# Testpoints.net
KiCad netlist of a schematic drawn in Altium Designer
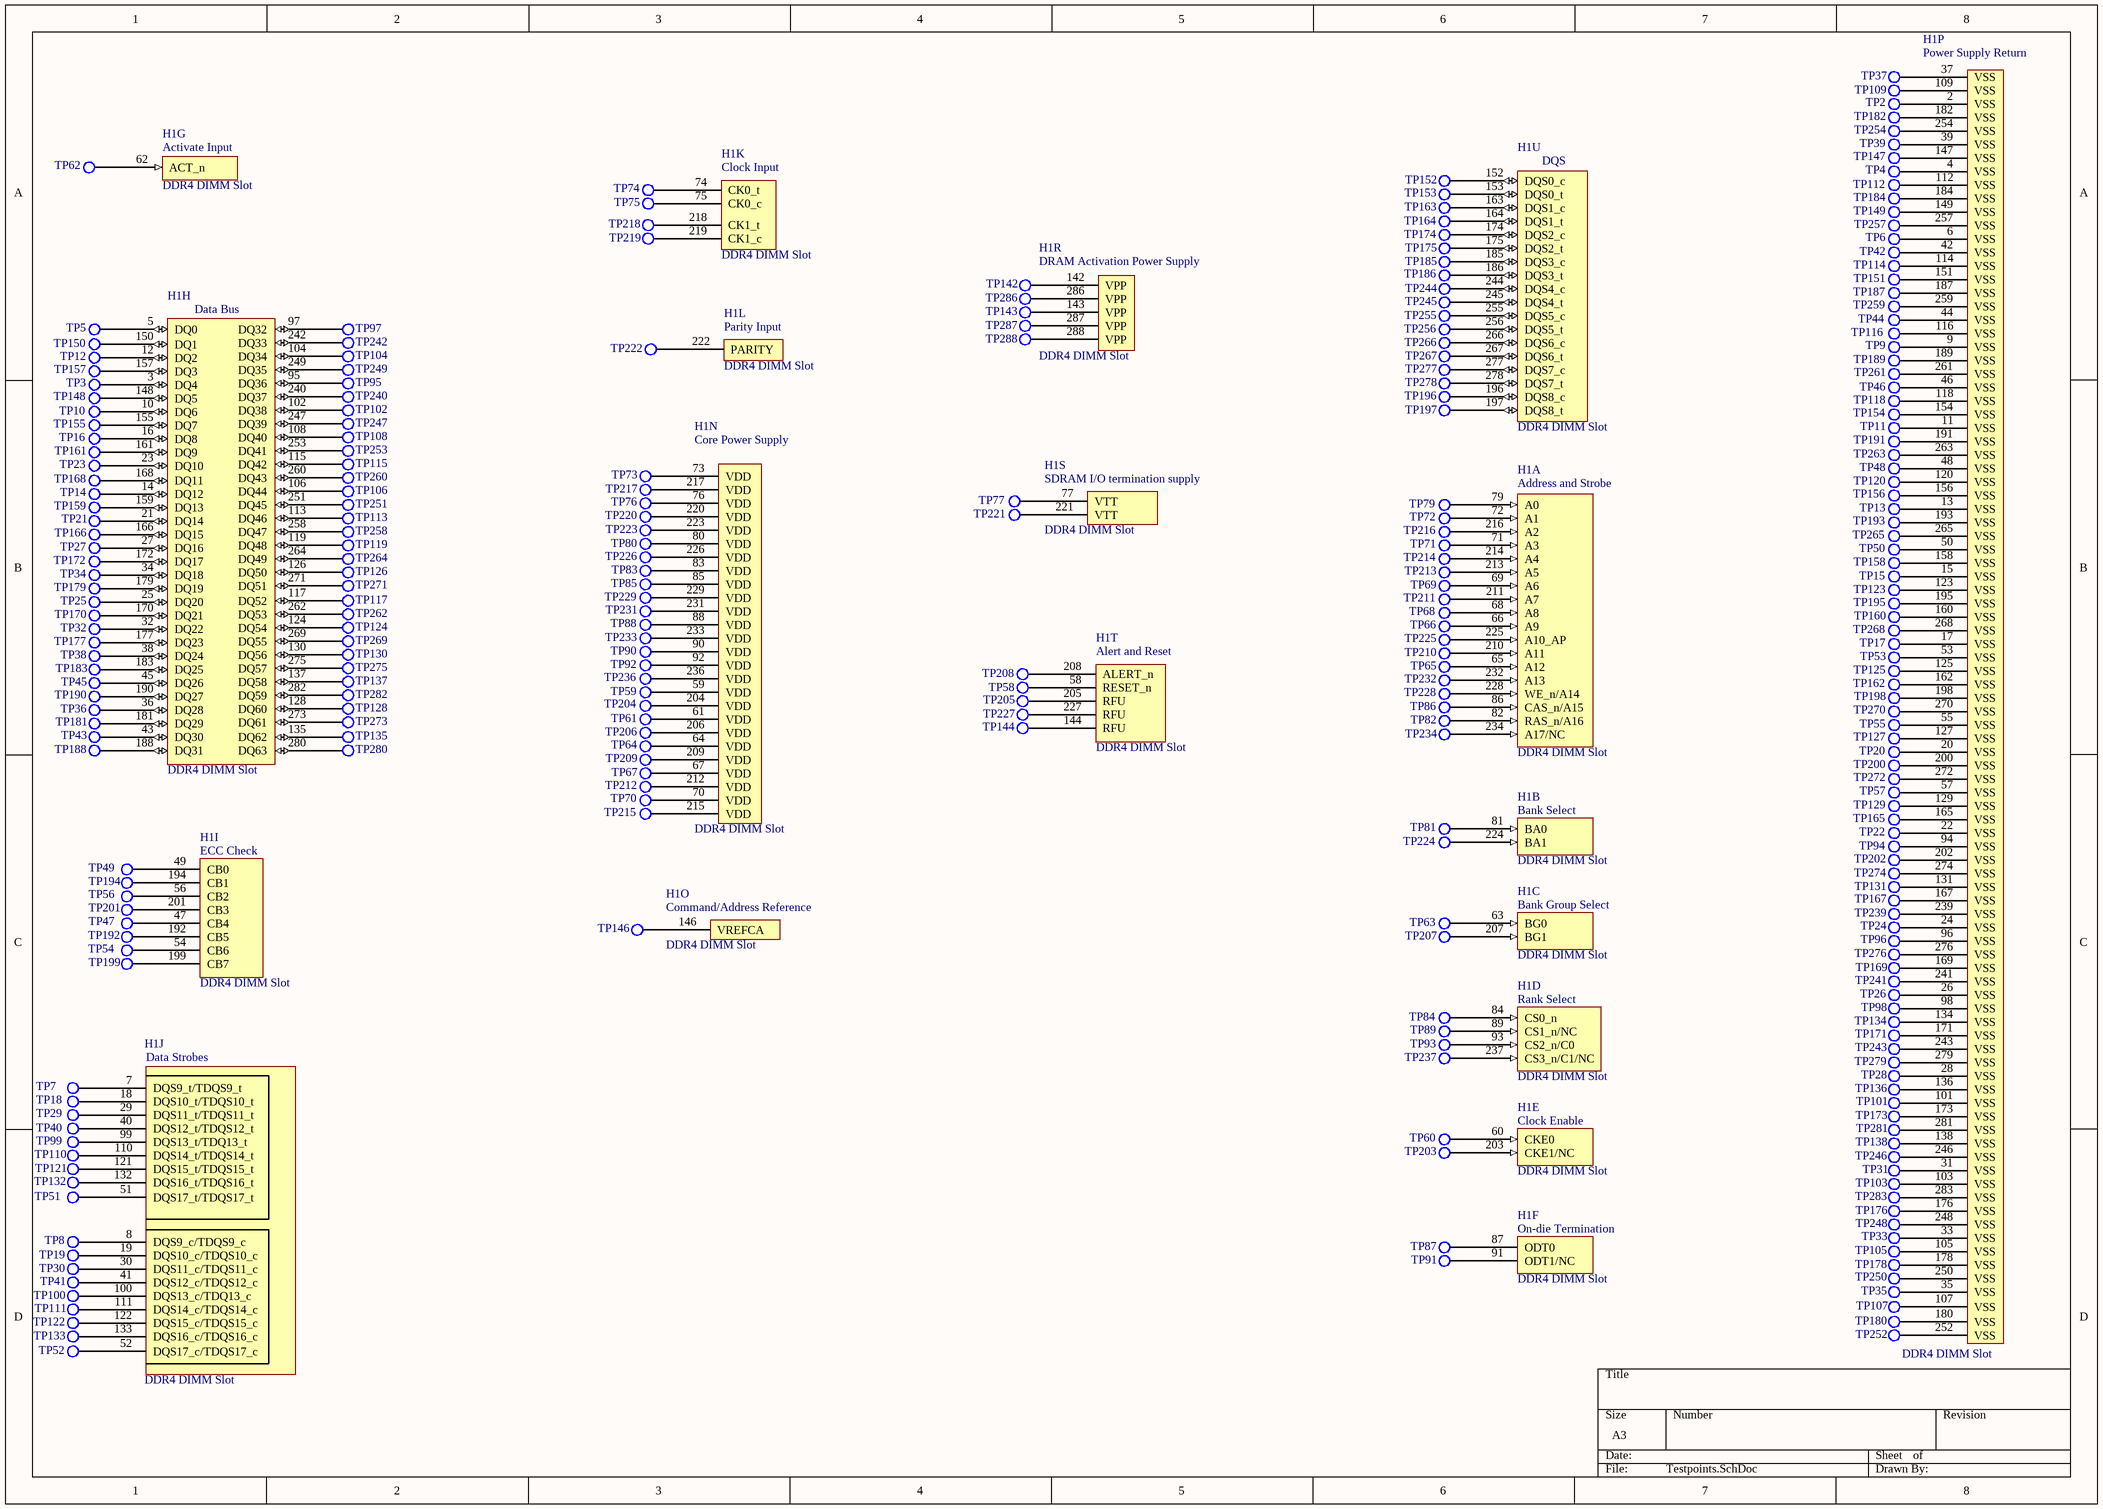
[diagram p0: Testpoints.SchDoc]

(export (version "E")
  (design (tool "Eeschema 10.0.6"))
  (components
    (comp (ref "H1")
      (value "DDR4 DIMM Slot")
      (footprint "DDR4 DIMM Slot")
      (libsource (lib "RouterIntLib") (part "DDR4 DIMM Slot"))
    )
    (comp (ref "TP2")
      (value "Test Point")
      (footprint "Test Point")
      (libsource (lib "RouterIntLib") (part "Test Point"))
    )
    (comp (ref "TP3")
      (value "Test Point")
      (footprint "Test Point")
      (libsource (lib "RouterIntLib") (part "Test Point"))
    )
    (comp (ref "TP4")
      (value "Test Point")
      (footprint "Test Point")
      (libsource (lib "RouterIntLib") (part "Test Point"))
    )
    (comp (ref "TP5")
      (value "Test Point")
      (footprint "Test Point")
      (libsource (lib "RouterIntLib") (part "Test Point"))
    )
    (comp (ref "TP6")
      (value "Test Point")
      (footprint "Test Point")
      (libsource (lib "RouterIntLib") (part "Test Point"))
    )
    (comp (ref "TP7")
      (value "Test Point")
      (footprint "Test Point")
      (libsource (lib "RouterIntLib") (part "Test Point"))
    )
    (comp (ref "TP8")
      (value "Test Point")
      (footprint "Test Point")
      (libsource (lib "RouterIntLib") (part "Test Point"))
    )
    (comp (ref "TP9")
      (value "Test Point")
      (footprint "Test Point")
      (libsource (lib "RouterIntLib") (part "Test Point"))
    )
    (comp (ref "TP10")
      (value "Test Point")
      (footprint "Test Point")
      (libsource (lib "RouterIntLib") (part "Test Point"))
    )
    (comp (ref "TP11")
      (value "Test Point")
      (footprint "Test Point")
      (libsource (lib "RouterIntLib") (part "Test Point"))
    )
    (comp (ref "TP12")
      (value "Test Point")
      (footprint "Test Point")
      (libsource (lib "RouterIntLib") (part "Test Point"))
    )
    (comp (ref "TP13")
      (value "Test Point")
      (footprint "Test Point")
      (libsource (lib "RouterIntLib") (part "Test Point"))
    )
    (comp (ref "TP14")
      (value "Test Point")
      (footprint "Test Point")
      (libsource (lib "RouterIntLib") (part "Test Point"))
    )
    (comp (ref "TP15")
      (value "Test Point")
      (footprint "Test Point")
      (libsource (lib "RouterIntLib") (part "Test Point"))
    )
    (comp (ref "TP16")
      (value "Test Point")
      (footprint "Test Point")
      (libsource (lib "RouterIntLib") (part "Test Point"))
    )
    (comp (ref "TP17")
      (value "Test Point")
      (footprint "Test Point")
      (libsource (lib "RouterIntLib") (part "Test Point"))
    )
    (comp (ref "TP18")
      (value "Test Point")
      (footprint "Test Point")
      (libsource (lib "RouterIntLib") (part "Test Point"))
    )
    (comp (ref "TP19")
      (value "Test Point")
      (footprint "Test Point")
      (libsource (lib "RouterIntLib") (part "Test Point"))
    )
    (comp (ref "TP20")
      (value "Test Point")
      (footprint "Test Point")
      (libsource (lib "RouterIntLib") (part "Test Point"))
    )
    (comp (ref "TP21")
      (value "Test Point")
      (footprint "Test Point")
      (libsource (lib "RouterIntLib") (part "Test Point"))
    )
    (comp (ref "TP22")
      (value "Test Point")
      (footprint "Test Point")
      (libsource (lib "RouterIntLib") (part "Test Point"))
    )
    (comp (ref "TP23")
      (value "Test Point")
      (footprint "Test Point")
      (libsource (lib "RouterIntLib") (part "Test Point"))
    )
    (comp (ref "TP24")
      (value "Test Point")
      (footprint "Test Point")
      (libsource (lib "RouterIntLib") (part "Test Point"))
    )
    (comp (ref "TP25")
      (value "Test Point")
      (footprint "Test Point")
      (libsource (lib "RouterIntLib") (part "Test Point"))
    )
    (comp (ref "TP26")
      (value "Test Point")
      (footprint "Test Point")
      (libsource (lib "RouterIntLib") (part "Test Point"))
    )
    (comp (ref "TP27")
      (value "Test Point")
      (footprint "Test Point")
      (libsource (lib "RouterIntLib") (part "Test Point"))
    )
    (comp (ref "TP28")
      (value "Test Point")
      (footprint "Test Point")
      (libsource (lib "RouterIntLib") (part "Test Point"))
    )
    (comp (ref "TP29")
      (value "Test Point")
      (footprint "Test Point")
      (libsource (lib "RouterIntLib") (part "Test Point"))
    )
    (comp (ref "TP30")
      (value "Test Point")
      (footprint "Test Point")
      (libsource (lib "RouterIntLib") (part "Test Point"))
    )
    (comp (ref "TP31")
      (value "Test Point")
      (footprint "Test Point")
      (libsource (lib "RouterIntLib") (part "Test Point"))
    )
    (comp (ref "TP32")
      (value "Test Point")
      (footprint "Test Point")
      (libsource (lib "RouterIntLib") (part "Test Point"))
    )
    (comp (ref "TP33")
      (value "Test Point")
      (footprint "Test Point")
      (libsource (lib "RouterIntLib") (part "Test Point"))
    )
    (comp (ref "TP34")
      (value "Test Point")
      (footprint "Test Point")
      (libsource (lib "RouterIntLib") (part "Test Point"))
    )
    (comp (ref "TP35")
      (value "Test Point")
      (footprint "Test Point")
      (libsource (lib "RouterIntLib") (part "Test Point"))
    )
    (comp (ref "TP36")
      (value "Test Point")
      (footprint "Test Point")
      (libsource (lib "RouterIntLib") (part "Test Point"))
    )
    (comp (ref "TP37")
      (value "Test Point")
      (footprint "Test Point")
      (libsource (lib "RouterIntLib") (part "Test Point"))
    )
    (comp (ref "TP38")
      (value "Test Point")
      (footprint "Test Point")
      (libsource (lib "RouterIntLib") (part "Test Point"))
    )
    (comp (ref "TP39")
      (value "Test Point")
      (footprint "Test Point")
      (libsource (lib "RouterIntLib") (part "Test Point"))
    )
    (comp (ref "TP40")
      (value "Test Point")
      (footprint "Test Point")
      (libsource (lib "RouterIntLib") (part "Test Point"))
    )
    (comp (ref "TP41")
      (value "Test Point")
      (footprint "Test Point")
      (libsource (lib "RouterIntLib") (part "Test Point"))
    )
    (comp (ref "TP42")
      (value "Test Point")
      (footprint "Test Point")
      (libsource (lib "RouterIntLib") (part "Test Point"))
    )
    (comp (ref "TP43")
      (value "Test Point")
      (footprint "Test Point")
      (libsource (lib "RouterIntLib") (part "Test Point"))
    )
    (comp (ref "TP44")
      (value "Test Point")
      (footprint "Test Point")
      (libsource (lib "RouterIntLib") (part "Test Point"))
    )
    (comp (ref "TP45")
      (value "Test Point")
      (footprint "Test Point")
      (libsource (lib "RouterIntLib") (part "Test Point"))
    )
    (comp (ref "TP46")
      (value "Test Point")
      (footprint "Test Point")
      (libsource (lib "RouterIntLib") (part "Test Point"))
    )
    (comp (ref "TP47")
      (value "Test Point")
      (footprint "Test Point")
      (libsource (lib "RouterIntLib") (part "Test Point"))
    )
    (comp (ref "TP48")
      (value "Test Point")
      (footprint "Test Point")
      (libsource (lib "RouterIntLib") (part "Test Point"))
    )
    (comp (ref "TP49")
      (value "Test Point")
      (footprint "Test Point")
      (libsource (lib "RouterIntLib") (part "Test Point"))
    )
    (comp (ref "TP50")
      (value "Test Point")
      (footprint "Test Point")
      (libsource (lib "RouterIntLib") (part "Test Point"))
    )
    (comp (ref "TP51")
      (value "Test Point")
      (footprint "Test Point")
      (libsource (lib "RouterIntLib") (part "Test Point"))
    )
    (comp (ref "TP52")
      (value "Test Point")
      (footprint "Test Point")
      (libsource (lib "RouterIntLib") (part "Test Point"))
    )
    (comp (ref "TP53")
      (value "Test Point")
      (footprint "Test Point")
      (libsource (lib "RouterIntLib") (part "Test Point"))
    )
    (comp (ref "TP54")
      (value "Test Point")
      (footprint "Test Point")
      (libsource (lib "RouterIntLib") (part "Test Point"))
    )
    (comp (ref "TP55")
      (value "Test Point")
      (footprint "Test Point")
      (libsource (lib "RouterIntLib") (part "Test Point"))
    )
    (comp (ref "TP56")
      (value "Test Point")
      (footprint "Test Point")
      (libsource (lib "RouterIntLib") (part "Test Point"))
    )
    (comp (ref "TP57")
      (value "Test Point")
      (footprint "Test Point")
      (libsource (lib "RouterIntLib") (part "Test Point"))
    )
    (comp (ref "TP58")
      (value "Test Point")
      (footprint "Test Point")
      (libsource (lib "RouterIntLib") (part "Test Point"))
    )
    (comp (ref "TP59")
      (value "Test Point")
      (footprint "Test Point")
      (libsource (lib "RouterIntLib") (part "Test Point"))
    )
    (comp (ref "TP60")
      (value "Test Point")
      (footprint "Test Point")
      (libsource (lib "RouterIntLib") (part "Test Point"))
    )
    (comp (ref "TP61")
      (value "Test Point")
      (footprint "Test Point")
      (libsource (lib "RouterIntLib") (part "Test Point"))
    )
    (comp (ref "TP62")
      (value "Test Point")
      (footprint "Test Point")
      (libsource (lib "RouterIntLib") (part "Test Point"))
    )
    (comp (ref "TP63")
      (value "Test Point")
      (footprint "Test Point")
      (libsource (lib "RouterIntLib") (part "Test Point"))
    )
    (comp (ref "TP64")
      (value "Test Point")
      (footprint "Test Point")
      (libsource (lib "RouterIntLib") (part "Test Point"))
    )
    (comp (ref "TP65")
      (value "Test Point")
      (footprint "Test Point")
      (libsource (lib "RouterIntLib") (part "Test Point"))
    )
    (comp (ref "TP66")
      (value "Test Point")
      (footprint "Test Point")
      (libsource (lib "RouterIntLib") (part "Test Point"))
    )
    (comp (ref "TP67")
      (value "Test Point")
      (footprint "Test Point")
      (libsource (lib "RouterIntLib") (part "Test Point"))
    )
    (comp (ref "TP68")
      (value "Test Point")
      (footprint "Test Point")
      (libsource (lib "RouterIntLib") (part "Test Point"))
    )
    (comp (ref "TP69")
      (value "Test Point")
      (footprint "Test Point")
      (libsource (lib "RouterIntLib") (part "Test Point"))
    )
    (comp (ref "TP70")
      (value "Test Point")
      (footprint "Test Point")
      (libsource (lib "RouterIntLib") (part "Test Point"))
    )
    (comp (ref "TP71")
      (value "Test Point")
      (footprint "Test Point")
      (libsource (lib "RouterIntLib") (part "Test Point"))
    )
    (comp (ref "TP72")
      (value "Test Point")
      (footprint "Test Point")
      (libsource (lib "RouterIntLib") (part "Test Point"))
    )
    (comp (ref "TP73")
      (value "Test Point")
      (footprint "Test Point")
      (libsource (lib "RouterIntLib") (part "Test Point"))
    )
    (comp (ref "TP74")
      (value "Test Point")
      (footprint "Test Point")
      (libsource (lib "RouterIntLib") (part "Test Point"))
    )
    (comp (ref "TP75")
      (value "Test Point")
      (footprint "Test Point")
      (libsource (lib "RouterIntLib") (part "Test Point"))
    )
    (comp (ref "TP76")
      (value "Test Point")
      (footprint "Test Point")
      (libsource (lib "RouterIntLib") (part "Test Point"))
    )
    (comp (ref "TP77")
      (value "Test Point")
      (footprint "Test Point")
      (libsource (lib "RouterIntLib") (part "Test Point"))
    )
    (comp (ref "TP79")
      (value "Test Point")
      (footprint "Test Point")
      (libsource (lib "RouterIntLib") (part "Test Point"))
    )
    (comp (ref "TP80")
      (value "Test Point")
      (footprint "Test Point")
      (libsource (lib "RouterIntLib") (part "Test Point"))
    )
    (comp (ref "TP81")
      (value "Test Point")
      (footprint "Test Point")
      (libsource (lib "RouterIntLib") (part "Test Point"))
    )
    (comp (ref "TP82")
      (value "Test Point")
      (footprint "Test Point")
      (libsource (lib "RouterIntLib") (part "Test Point"))
    )
    (comp (ref "TP83")
      (value "Test Point")
      (footprint "Test Point")
      (libsource (lib "RouterIntLib") (part "Test Point"))
    )
    (comp (ref "TP84")
      (value "Test Point")
      (footprint "Test Point")
      (libsource (lib "RouterIntLib") (part "Test Point"))
    )
    (comp (ref "TP85")
      (value "Test Point")
      (footprint "Test Point")
      (libsource (lib "RouterIntLib") (part "Test Point"))
    )
    (comp (ref "TP86")
      (value "Test Point")
      (footprint "Test Point")
      (libsource (lib "RouterIntLib") (part "Test Point"))
    )
    (comp (ref "TP87")
      (value "Test Point")
      (footprint "Test Point")
      (libsource (lib "RouterIntLib") (part "Test Point"))
    )
    (comp (ref "TP88")
      (value "Test Point")
      (footprint "Test Point")
      (libsource (lib "RouterIntLib") (part "Test Point"))
    )
    (comp (ref "TP89")
      (value "Test Point")
      (footprint "Test Point")
      (libsource (lib "RouterIntLib") (part "Test Point"))
    )
    (comp (ref "TP90")
      (value "Test Point")
      (footprint "Test Point")
      (libsource (lib "RouterIntLib") (part "Test Point"))
    )
    (comp (ref "TP91")
      (value "Test Point")
      (footprint "Test Point")
      (libsource (lib "RouterIntLib") (part "Test Point"))
    )
    (comp (ref "TP92")
      (value "Test Point")
      (footprint "Test Point")
      (libsource (lib "RouterIntLib") (part "Test Point"))
    )
    (comp (ref "TP93")
      (value "Test Point")
      (footprint "Test Point")
      (libsource (lib "RouterIntLib") (part "Test Point"))
    )
    (comp (ref "TP94")
      (value "Test Point")
      (footprint "Test Point")
      (libsource (lib "RouterIntLib") (part "Test Point"))
    )
    (comp (ref "TP95")
      (value "Test Point")
      (footprint "Test Point")
      (libsource (lib "RouterIntLib") (part "Test Point"))
    )
    (comp (ref "TP96")
      (value "Test Point")
      (footprint "Test Point")
      (libsource (lib "RouterIntLib") (part "Test Point"))
    )
    (comp (ref "TP97")
      (value "Test Point")
      (footprint "Test Point")
      (libsource (lib "RouterIntLib") (part "Test Point"))
    )
    (comp (ref "TP98")
      (value "Test Point")
      (footprint "Test Point")
      (libsource (lib "RouterIntLib") (part "Test Point"))
    )
    (comp (ref "TP99")
      (value "Test Point")
      (footprint "Test Point")
      (libsource (lib "RouterIntLib") (part "Test Point"))
    )
    (comp (ref "TP100")
      (value "Test Point")
      (footprint "Test Point")
      (libsource (lib "RouterIntLib") (part "Test Point"))
    )
    (comp (ref "TP101")
      (value "Test Point")
      (footprint "Test Point")
      (libsource (lib "RouterIntLib") (part "Test Point"))
    )
    (comp (ref "TP102")
      (value "Test Point")
      (footprint "Test Point")
      (libsource (lib "RouterIntLib") (part "Test Point"))
    )
    (comp (ref "TP103")
      (value "Test Point")
      (footprint "Test Point")
      (libsource (lib "RouterIntLib") (part "Test Point"))
    )
    (comp (ref "TP104")
      (value "Test Point")
      (footprint "Test Point")
      (libsource (lib "RouterIntLib") (part "Test Point"))
    )
    (comp (ref "TP105")
      (value "Test Point")
      (footprint "Test Point")
      (libsource (lib "RouterIntLib") (part "Test Point"))
    )
    (comp (ref "TP106")
      (value "Test Point")
      (footprint "Test Point")
      (libsource (lib "RouterIntLib") (part "Test Point"))
    )
    (comp (ref "TP107")
      (value "Test Point")
      (footprint "Test Point")
      (libsource (lib "RouterIntLib") (part "Test Point"))
    )
    (comp (ref "TP108")
      (value "Test Point")
      (footprint "Test Point")
      (libsource (lib "RouterIntLib") (part "Test Point"))
    )
    (comp (ref "TP109")
      (value "Test Point")
      (footprint "Test Point")
      (libsource (lib "RouterIntLib") (part "Test Point"))
    )
    (comp (ref "TP110")
      (value "Test Point")
      (footprint "Test Point")
      (libsource (lib "RouterIntLib") (part "Test Point"))
    )
    (comp (ref "TP111")
      (value "Test Point")
      (footprint "Test Point")
      (libsource (lib "RouterIntLib") (part "Test Point"))
    )
    (comp (ref "TP112")
      (value "Test Point")
      (footprint "Test Point")
      (libsource (lib "RouterIntLib") (part "Test Point"))
    )
    (comp (ref "TP113")
      (value "Test Point")
      (footprint "Test Point")
      (libsource (lib "RouterIntLib") (part "Test Point"))
    )
    (comp (ref "TP114")
      (value "Test Point")
      (footprint "Test Point")
      (libsource (lib "RouterIntLib") (part "Test Point"))
    )
    (comp (ref "TP115")
      (value "Test Point")
      (footprint "Test Point")
      (libsource (lib "RouterIntLib") (part "Test Point"))
    )
    (comp (ref "TP116")
      (value "Test Point")
      (footprint "Test Point")
      (libsource (lib "RouterIntLib") (part "Test Point"))
    )
    (comp (ref "TP117")
      (value "Test Point")
      (footprint "Test Point")
      (libsource (lib "RouterIntLib") (part "Test Point"))
    )
    (comp (ref "TP118")
      (value "Test Point")
      (footprint "Test Point")
      (libsource (lib "RouterIntLib") (part "Test Point"))
    )
    (comp (ref "TP119")
      (value "Test Point")
      (footprint "Test Point")
      (libsource (lib "RouterIntLib") (part "Test Point"))
    )
    (comp (ref "TP120")
      (value "Test Point")
      (footprint "Test Point")
      (libsource (lib "RouterIntLib") (part "Test Point"))
    )
    (comp (ref "TP121")
      (value "Test Point")
      (footprint "Test Point")
      (libsource (lib "RouterIntLib") (part "Test Point"))
    )
    (comp (ref "TP122")
      (value "Test Point")
      (footprint "Test Point")
      (libsource (lib "RouterIntLib") (part "Test Point"))
    )
    (comp (ref "TP123")
      (value "Test Point")
      (footprint "Test Point")
      (libsource (lib "RouterIntLib") (part "Test Point"))
    )
    (comp (ref "TP124")
      (value "Test Point")
      (footprint "Test Point")
      (libsource (lib "RouterIntLib") (part "Test Point"))
    )
    (comp (ref "TP125")
      (value "Test Point")
      (footprint "Test Point")
      (libsource (lib "RouterIntLib") (part "Test Point"))
    )
    (comp (ref "TP126")
      (value "Test Point")
      (footprint "Test Point")
      (libsource (lib "RouterIntLib") (part "Test Point"))
    )
    (comp (ref "TP127")
      (value "Test Point")
      (footprint "Test Point")
      (libsource (lib "RouterIntLib") (part "Test Point"))
    )
    (comp (ref "TP128")
      (value "Test Point")
      (footprint "Test Point")
      (libsource (lib "RouterIntLib") (part "Test Point"))
    )
    (comp (ref "TP129")
      (value "Test Point")
      (footprint "Test Point")
      (libsource (lib "RouterIntLib") (part "Test Point"))
    )
    (comp (ref "TP130")
      (value "Test Point")
      (footprint "Test Point")
      (libsource (lib "RouterIntLib") (part "Test Point"))
    )
    (comp (ref "TP131")
      (value "Test Point")
      (footprint "Test Point")
      (libsource (lib "RouterIntLib") (part "Test Point"))
    )
    (comp (ref "TP132")
      (value "Test Point")
      (footprint "Test Point")
      (libsource (lib "RouterIntLib") (part "Test Point"))
    )
    (comp (ref "TP133")
      (value "Test Point")
      (footprint "Test Point")
      (libsource (lib "RouterIntLib") (part "Test Point"))
    )
    (comp (ref "TP134")
      (value "Test Point")
      (footprint "Test Point")
      (libsource (lib "RouterIntLib") (part "Test Point"))
    )
    (comp (ref "TP135")
      (value "Test Point")
      (footprint "Test Point")
      (libsource (lib "RouterIntLib") (part "Test Point"))
    )
    (comp (ref "TP136")
      (value "Test Point")
      (footprint "Test Point")
      (libsource (lib "RouterIntLib") (part "Test Point"))
    )
    (comp (ref "TP137")
      (value "Test Point")
      (footprint "Test Point")
      (libsource (lib "RouterIntLib") (part "Test Point"))
    )
    (comp (ref "TP138")
      (value "Test Point")
      (footprint "Test Point")
      (libsource (lib "RouterIntLib") (part "Test Point"))
    )
    (comp (ref "TP142")
      (value "Test Point")
      (footprint "Test Point")
      (libsource (lib "RouterIntLib") (part "Test Point"))
    )
    (comp (ref "TP143")
      (value "Test Point")
      (footprint "Test Point")
      (libsource (lib "RouterIntLib") (part "Test Point"))
    )
    (comp (ref "TP144")
      (value "Test Point")
      (footprint "Test Point")
      (libsource (lib "RouterIntLib") (part "Test Point"))
    )
    (comp (ref "TP146")
      (value "Test Point")
      (footprint "Test Point")
      (libsource (lib "RouterIntLib") (part "Test Point"))
    )
    (comp (ref "TP147")
      (value "Test Point")
      (footprint "Test Point")
      (libsource (lib "RouterIntLib") (part "Test Point"))
    )
    (comp (ref "TP148")
      (value "Test Point")
      (footprint "Test Point")
      (libsource (lib "RouterIntLib") (part "Test Point"))
    )
    (comp (ref "TP149")
      (value "Test Point")
      (footprint "Test Point")
      (libsource (lib "RouterIntLib") (part "Test Point"))
    )
    (comp (ref "TP150")
      (value "Test Point")
      (footprint "Test Point")
      (libsource (lib "RouterIntLib") (part "Test Point"))
    )
    (comp (ref "TP151")
      (value "Test Point")
      (footprint "Test Point")
      (libsource (lib "RouterIntLib") (part "Test Point"))
    )
    (comp (ref "TP152")
      (value "Test Point")
      (footprint "Test Point")
      (libsource (lib "RouterIntLib") (part "Test Point"))
    )
    (comp (ref "TP153")
      (value "Test Point")
      (footprint "Test Point")
      (libsource (lib "RouterIntLib") (part "Test Point"))
    )
    (comp (ref "TP154")
      (value "Test Point")
      (footprint "Test Point")
      (libsource (lib "RouterIntLib") (part "Test Point"))
    )
    (comp (ref "TP155")
      (value "Test Point")
      (footprint "Test Point")
      (libsource (lib "RouterIntLib") (part "Test Point"))
    )
    (comp (ref "TP156")
      (value "Test Point")
      (footprint "Test Point")
      (libsource (lib "RouterIntLib") (part "Test Point"))
    )
    (comp (ref "TP157")
      (value "Test Point")
      (footprint "Test Point")
      (libsource (lib "RouterIntLib") (part "Test Point"))
    )
    (comp (ref "TP158")
      (value "Test Point")
      (footprint "Test Point")
      (libsource (lib "RouterIntLib") (part "Test Point"))
    )
    (comp (ref "TP159")
      (value "Test Point")
      (footprint "Test Point")
      (libsource (lib "RouterIntLib") (part "Test Point"))
    )
    (comp (ref "TP160")
      (value "Test Point")
      (footprint "Test Point")
      (libsource (lib "RouterIntLib") (part "Test Point"))
    )
    (comp (ref "TP161")
      (value "Test Point")
      (footprint "Test Point")
      (libsource (lib "RouterIntLib") (part "Test Point"))
    )
    (comp (ref "TP162")
      (value "Test Point")
      (footprint "Test Point")
      (libsource (lib "RouterIntLib") (part "Test Point"))
    )
    (comp (ref "TP163")
      (value "Test Point")
      (footprint "Test Point")
      (libsource (lib "RouterIntLib") (part "Test Point"))
    )
    (comp (ref "TP164")
      (value "Test Point")
      (footprint "Test Point")
      (libsource (lib "RouterIntLib") (part "Test Point"))
    )
    (comp (ref "TP165")
      (value "Test Point")
      (footprint "Test Point")
      (libsource (lib "RouterIntLib") (part "Test Point"))
    )
    (comp (ref "TP166")
      (value "Test Point")
      (footprint "Test Point")
      (libsource (lib "RouterIntLib") (part "Test Point"))
    )
    (comp (ref "TP167")
      (value "Test Point")
      (footprint "Test Point")
      (libsource (lib "RouterIntLib") (part "Test Point"))
    )
    (comp (ref "TP168")
      (value "Test Point")
      (footprint "Test Point")
      (libsource (lib "RouterIntLib") (part "Test Point"))
    )
    (comp (ref "TP169")
      (value "Test Point")
      (footprint "Test Point")
      (libsource (lib "RouterIntLib") (part "Test Point"))
    )
    (comp (ref "TP170")
      (value "Test Point")
      (footprint "Test Point")
      (libsource (lib "RouterIntLib") (part "Test Point"))
    )
    (comp (ref "TP171")
      (value "Test Point")
      (footprint "Test Point")
      (libsource (lib "RouterIntLib") (part "Test Point"))
    )
    (comp (ref "TP172")
      (value "Test Point")
      (footprint "Test Point")
      (libsource (lib "RouterIntLib") (part "Test Point"))
    )
    (comp (ref "TP173")
      (value "Test Point")
      (footprint "Test Point")
      (libsource (lib "RouterIntLib") (part "Test Point"))
    )
    (comp (ref "TP174")
      (value "Test Point")
      (footprint "Test Point")
      (libsource (lib "RouterIntLib") (part "Test Point"))
    )
    (comp (ref "TP175")
      (value "Test Point")
      (footprint "Test Point")
      (libsource (lib "RouterIntLib") (part "Test Point"))
    )
    (comp (ref "TP176")
      (value "Test Point")
      (footprint "Test Point")
      (libsource (lib "RouterIntLib") (part "Test Point"))
    )
    (comp (ref "TP177")
      (value "Test Point")
      (footprint "Test Point")
      (libsource (lib "RouterIntLib") (part "Test Point"))
    )
    (comp (ref "TP178")
      (value "Test Point")
      (footprint "Test Point")
      (libsource (lib "RouterIntLib") (part "Test Point"))
    )
    (comp (ref "TP179")
      (value "Test Point")
      (footprint "Test Point")
      (libsource (lib "RouterIntLib") (part "Test Point"))
    )
    (comp (ref "TP180")
      (value "Test Point")
      (footprint "Test Point")
      (libsource (lib "RouterIntLib") (part "Test Point"))
    )
    (comp (ref "TP181")
      (value "Test Point")
      (footprint "Test Point")
      (libsource (lib "RouterIntLib") (part "Test Point"))
    )
    (comp (ref "TP182")
      (value "Test Point")
      (footprint "Test Point")
      (libsource (lib "RouterIntLib") (part "Test Point"))
    )
    (comp (ref "TP183")
      (value "Test Point")
      (footprint "Test Point")
      (libsource (lib "RouterIntLib") (part "Test Point"))
    )
    (comp (ref "TP184")
      (value "Test Point")
      (footprint "Test Point")
      (libsource (lib "RouterIntLib") (part "Test Point"))
    )
    (comp (ref "TP185")
      (value "Test Point")
      (footprint "Test Point")
      (libsource (lib "RouterIntLib") (part "Test Point"))
    )
    (comp (ref "TP186")
      (value "Test Point")
      (footprint "Test Point")
      (libsource (lib "RouterIntLib") (part "Test Point"))
    )
    (comp (ref "TP187")
      (value "Test Point")
      (footprint "Test Point")
      (libsource (lib "RouterIntLib") (part "Test Point"))
    )
    (comp (ref "TP188")
      (value "Test Point")
      (footprint "Test Point")
      (libsource (lib "RouterIntLib") (part "Test Point"))
    )
    (comp (ref "TP189")
      (value "Test Point")
      (footprint "Test Point")
      (libsource (lib "RouterIntLib") (part "Test Point"))
    )
    (comp (ref "TP190")
      (value "Test Point")
      (footprint "Test Point")
      (libsource (lib "RouterIntLib") (part "Test Point"))
    )
    (comp (ref "TP191")
      (value "Test Point")
      (footprint "Test Point")
      (libsource (lib "RouterIntLib") (part "Test Point"))
    )
    (comp (ref "TP192")
      (value "Test Point")
      (footprint "Test Point")
      (libsource (lib "RouterIntLib") (part "Test Point"))
    )
    (comp (ref "TP193")
      (value "Test Point")
      (footprint "Test Point")
      (libsource (lib "RouterIntLib") (part "Test Point"))
    )
    (comp (ref "TP194")
      (value "Test Point")
      (footprint "Test Point")
      (libsource (lib "RouterIntLib") (part "Test Point"))
    )
    (comp (ref "TP195")
      (value "Test Point")
      (footprint "Test Point")
      (libsource (lib "RouterIntLib") (part "Test Point"))
    )
    (comp (ref "TP196")
      (value "Test Point")
      (footprint "Test Point")
      (libsource (lib "RouterIntLib") (part "Test Point"))
    )
    (comp (ref "TP197")
      (value "Test Point")
      (footprint "Test Point")
      (libsource (lib "RouterIntLib") (part "Test Point"))
    )
    (comp (ref "TP198")
      (value "Test Point")
      (footprint "Test Point")
      (libsource (lib "RouterIntLib") (part "Test Point"))
    )
    (comp (ref "TP199")
      (value "Test Point")
      (footprint "Test Point")
      (libsource (lib "RouterIntLib") (part "Test Point"))
    )
    (comp (ref "TP200")
      (value "Test Point")
      (footprint "Test Point")
      (libsource (lib "RouterIntLib") (part "Test Point"))
    )
    (comp (ref "TP201")
      (value "Test Point")
      (footprint "Test Point")
      (libsource (lib "RouterIntLib") (part "Test Point"))
    )
    (comp (ref "TP202")
      (value "Test Point")
      (footprint "Test Point")
      (libsource (lib "RouterIntLib") (part "Test Point"))
    )
    (comp (ref "TP203")
      (value "Test Point")
      (footprint "Test Point")
      (libsource (lib "RouterIntLib") (part "Test Point"))
    )
    (comp (ref "TP204")
      (value "Test Point")
      (footprint "Test Point")
      (libsource (lib "RouterIntLib") (part "Test Point"))
    )
    (comp (ref "TP205")
      (value "Test Point")
      (footprint "Test Point")
      (libsource (lib "RouterIntLib") (part "Test Point"))
    )
    (comp (ref "TP206")
      (value "Test Point")
      (footprint "Test Point")
      (libsource (lib "RouterIntLib") (part "Test Point"))
    )
    (comp (ref "TP207")
      (value "Test Point")
      (footprint "Test Point")
      (libsource (lib "RouterIntLib") (part "Test Point"))
    )
    (comp (ref "TP208")
      (value "Test Point")
      (footprint "Test Point")
      (libsource (lib "RouterIntLib") (part "Test Point"))
    )
    (comp (ref "TP209")
      (value "Test Point")
      (footprint "Test Point")
      (libsource (lib "RouterIntLib") (part "Test Point"))
    )
    (comp (ref "TP210")
      (value "Test Point")
      (footprint "Test Point")
      (libsource (lib "RouterIntLib") (part "Test Point"))
    )
    (comp (ref "TP211")
      (value "Test Point")
      (footprint "Test Point")
      (libsource (lib "RouterIntLib") (part "Test Point"))
    )
    (comp (ref "TP212")
      (value "Test Point")
      (footprint "Test Point")
      (libsource (lib "RouterIntLib") (part "Test Point"))
    )
    (comp (ref "TP213")
      (value "Test Point")
      (footprint "Test Point")
      (libsource (lib "RouterIntLib") (part "Test Point"))
    )
    (comp (ref "TP214")
      (value "Test Point")
      (footprint "Test Point")
      (libsource (lib "RouterIntLib") (part "Test Point"))
    )
    (comp (ref "TP215")
      (value "Test Point")
      (footprint "Test Point")
      (libsource (lib "RouterIntLib") (part "Test Point"))
    )
    (comp (ref "TP216")
      (value "Test Point")
      (footprint "Test Point")
      (libsource (lib "RouterIntLib") (part "Test Point"))
    )
    (comp (ref "TP217")
      (value "Test Point")
      (footprint "Test Point")
      (libsource (lib "RouterIntLib") (part "Test Point"))
    )
    (comp (ref "TP218")
      (value "Test Point")
      (footprint "Test Point")
      (libsource (lib "RouterIntLib") (part "Test Point"))
    )
    (comp (ref "TP219")
      (value "Test Point")
      (footprint "Test Point")
      (libsource (lib "RouterIntLib") (part "Test Point"))
    )
    (comp (ref "TP220")
      (value "Test Point")
      (footprint "Test Point")
      (libsource (lib "RouterIntLib") (part "Test Point"))
    )
    (comp (ref "TP221")
      (value "Test Point")
      (footprint "Test Point")
      (libsource (lib "RouterIntLib") (part "Test Point"))
    )
    (comp (ref "TP222")
      (value "Test Point")
      (footprint "Test Point")
      (libsource (lib "RouterIntLib") (part "Test Point"))
    )
    (comp (ref "TP223")
      (value "Test Point")
      (footprint "Test Point")
      (libsource (lib "RouterIntLib") (part "Test Point"))
    )
    (comp (ref "TP224")
      (value "Test Point")
      (footprint "Test Point")
      (libsource (lib "RouterIntLib") (part "Test Point"))
    )
    (comp (ref "TP225")
      (value "Test Point")
      (footprint "Test Point")
      (libsource (lib "RouterIntLib") (part "Test Point"))
    )
    (comp (ref "TP226")
      (value "Test Point")
      (footprint "Test Point")
      (libsource (lib "RouterIntLib") (part "Test Point"))
    )
    (comp (ref "TP227")
      (value "Test Point")
      (footprint "Test Point")
      (libsource (lib "RouterIntLib") (part "Test Point"))
    )
    (comp (ref "TP228")
      (value "Test Point")
      (footprint "Test Point")
      (libsource (lib "RouterIntLib") (part "Test Point"))
    )
    (comp (ref "TP229")
      (value "Test Point")
      (footprint "Test Point")
      (libsource (lib "RouterIntLib") (part "Test Point"))
    )
    (comp (ref "TP231")
      (value "Test Point")
      (footprint "Test Point")
      (libsource (lib "RouterIntLib") (part "Test Point"))
    )
    (comp (ref "TP232")
      (value "Test Point")
      (footprint "Test Point")
      (libsource (lib "RouterIntLib") (part "Test Point"))
    )
    (comp (ref "TP233")
      (value "Test Point")
      (footprint "Test Point")
      (libsource (lib "RouterIntLib") (part "Test Point"))
    )
    (comp (ref "TP234")
      (value "Test Point")
      (footprint "Test Point")
      (libsource (lib "RouterIntLib") (part "Test Point"))
    )
    (comp (ref "TP236")
      (value "Test Point")
      (footprint "Test Point")
      (libsource (lib "RouterIntLib") (part "Test Point"))
    )
    (comp (ref "TP237")
      (value "Test Point")
      (footprint "Test Point")
      (libsource (lib "RouterIntLib") (part "Test Point"))
    )
    (comp (ref "TP239")
      (value "Test Point")
      (footprint "Test Point")
      (libsource (lib "RouterIntLib") (part "Test Point"))
    )
    (comp (ref "TP240")
      (value "Test Point")
      (footprint "Test Point")
      (libsource (lib "RouterIntLib") (part "Test Point"))
    )
    (comp (ref "TP241")
      (value "Test Point")
      (footprint "Test Point")
      (libsource (lib "RouterIntLib") (part "Test Point"))
    )
    (comp (ref "TP242")
      (value "Test Point")
      (footprint "Test Point")
      (libsource (lib "RouterIntLib") (part "Test Point"))
    )
    (comp (ref "TP243")
      (value "Test Point")
      (footprint "Test Point")
      (libsource (lib "RouterIntLib") (part "Test Point"))
    )
    (comp (ref "TP244")
      (value "Test Point")
      (footprint "Test Point")
      (libsource (lib "RouterIntLib") (part "Test Point"))
    )
    (comp (ref "TP245")
      (value "Test Point")
      (footprint "Test Point")
      (libsource (lib "RouterIntLib") (part "Test Point"))
    )
    (comp (ref "TP246")
      (value "Test Point")
      (footprint "Test Point")
      (libsource (lib "RouterIntLib") (part "Test Point"))
    )
    (comp (ref "TP247")
      (value "Test Point")
      (footprint "Test Point")
      (libsource (lib "RouterIntLib") (part "Test Point"))
    )
    (comp (ref "TP248")
      (value "Test Point")
      (footprint "Test Point")
      (libsource (lib "RouterIntLib") (part "Test Point"))
    )
    (comp (ref "TP249")
      (value "Test Point")
      (footprint "Test Point")
      (libsource (lib "RouterIntLib") (part "Test Point"))
    )
    (comp (ref "TP250")
      (value "Test Point")
      (footprint "Test Point")
      (libsource (lib "RouterIntLib") (part "Test Point"))
    )
    (comp (ref "TP251")
      (value "Test Point")
      (footprint "Test Point")
      (libsource (lib "RouterIntLib") (part "Test Point"))
    )
    (comp (ref "TP252")
      (value "Test Point")
      (footprint "Test Point")
      (libsource (lib "RouterIntLib") (part "Test Point"))
    )
    (comp (ref "TP253")
      (value "Test Point")
      (footprint "Test Point")
      (libsource (lib "RouterIntLib") (part "Test Point"))
    )
    (comp (ref "TP254")
      (value "Test Point")
      (footprint "Test Point")
      (libsource (lib "RouterIntLib") (part "Test Point"))
    )
    (comp (ref "TP255")
      (value "Test Point")
      (footprint "Test Point")
      (libsource (lib "RouterIntLib") (part "Test Point"))
    )
    (comp (ref "TP256")
      (value "Test Point")
      (footprint "Test Point")
      (libsource (lib "RouterIntLib") (part "Test Point"))
    )
    (comp (ref "TP257")
      (value "Test Point")
      (footprint "Test Point")
      (libsource (lib "RouterIntLib") (part "Test Point"))
    )
    (comp (ref "TP258")
      (value "Test Point")
      (footprint "Test Point")
      (libsource (lib "RouterIntLib") (part "Test Point"))
    )
    (comp (ref "TP259")
      (value "Test Point")
      (footprint "Test Point")
      (libsource (lib "RouterIntLib") (part "Test Point"))
    )
    (comp (ref "TP260")
      (value "Test Point")
      (footprint "Test Point")
      (libsource (lib "RouterIntLib") (part "Test Point"))
    )
    (comp (ref "TP261")
      (value "Test Point")
      (footprint "Test Point")
      (libsource (lib "RouterIntLib") (part "Test Point"))
    )
    (comp (ref "TP262")
      (value "Test Point")
      (footprint "Test Point")
      (libsource (lib "RouterIntLib") (part "Test Point"))
    )
    (comp (ref "TP263")
      (value "Test Point")
      (footprint "Test Point")
      (libsource (lib "RouterIntLib") (part "Test Point"))
    )
    (comp (ref "TP264")
      (value "Test Point")
      (footprint "Test Point")
      (libsource (lib "RouterIntLib") (part "Test Point"))
    )
    (comp (ref "TP265")
      (value "Test Point")
      (footprint "Test Point")
      (libsource (lib "RouterIntLib") (part "Test Point"))
    )
    (comp (ref "TP266")
      (value "Test Point")
      (footprint "Test Point")
      (libsource (lib "RouterIntLib") (part "Test Point"))
    )
    (comp (ref "TP267")
      (value "Test Point")
      (footprint "Test Point")
      (libsource (lib "RouterIntLib") (part "Test Point"))
    )
    (comp (ref "TP268")
      (value "Test Point")
      (footprint "Test Point")
      (libsource (lib "RouterIntLib") (part "Test Point"))
    )
    (comp (ref "TP269")
      (value "Test Point")
      (footprint "Test Point")
      (libsource (lib "RouterIntLib") (part "Test Point"))
    )
    (comp (ref "TP270")
      (value "Test Point")
      (footprint "Test Point")
      (libsource (lib "RouterIntLib") (part "Test Point"))
    )
    (comp (ref "TP271")
      (value "Test Point")
      (footprint "Test Point")
      (libsource (lib "RouterIntLib") (part "Test Point"))
    )
    (comp (ref "TP272")
      (value "Test Point")
      (footprint "Test Point")
      (libsource (lib "RouterIntLib") (part "Test Point"))
    )
    (comp (ref "TP273")
      (value "Test Point")
      (footprint "Test Point")
      (libsource (lib "RouterIntLib") (part "Test Point"))
    )
    (comp (ref "TP274")
      (value "Test Point")
      (footprint "Test Point")
      (libsource (lib "RouterIntLib") (part "Test Point"))
    )
    (comp (ref "TP275")
      (value "Test Point")
      (footprint "Test Point")
      (libsource (lib "RouterIntLib") (part "Test Point"))
    )
    (comp (ref "TP276")
      (value "Test Point")
      (footprint "Test Point")
      (libsource (lib "RouterIntLib") (part "Test Point"))
    )
    (comp (ref "TP277")
      (value "Test Point")
      (footprint "Test Point")
      (libsource (lib "RouterIntLib") (part "Test Point"))
    )
    (comp (ref "TP278")
      (value "Test Point")
      (footprint "Test Point")
      (libsource (lib "RouterIntLib") (part "Test Point"))
    )
    (comp (ref "TP279")
      (value "Test Point")
      (footprint "Test Point")
      (libsource (lib "RouterIntLib") (part "Test Point"))
    )
    (comp (ref "TP280")
      (value "Test Point")
      (footprint "Test Point")
      (libsource (lib "RouterIntLib") (part "Test Point"))
    )
    (comp (ref "TP281")
      (value "Test Point")
      (footprint "Test Point")
      (libsource (lib "RouterIntLib") (part "Test Point"))
    )
    (comp (ref "TP282")
      (value "Test Point")
      (footprint "Test Point")
      (libsource (lib "RouterIntLib") (part "Test Point"))
    )
    (comp (ref "TP283")
      (value "Test Point")
      (footprint "Test Point")
      (libsource (lib "RouterIntLib") (part "Test Point"))
    )
    (comp (ref "TP286")
      (value "Test Point")
      (footprint "Test Point")
      (libsource (lib "RouterIntLib") (part "Test Point"))
    )
    (comp (ref "TP287")
      (value "Test Point")
      (footprint "Test Point")
      (libsource (lib "RouterIntLib") (part "Test Point"))
    )
    (comp (ref "TP288")
      (value "Test Point")
      (footprint "Test Point")
      (libsource (lib "RouterIntLib") (part "Test Point"))
    )
  )
  (nets
    (net (code "1") (name "Net-(H1A-A0)") (class "Default")
      (node (ref "H1") (pin "79") (pinfunction "A0_79") (pintype "input"))
      (node (ref "TP79") (pin "1") (pinfunction "1_1") (pintype "passive"))
    )
    (net (code "2") (name "Net-(H1A-A1)") (class "Default")
      (node (ref "H1") (pin "72") (pinfunction "A1_72") (pintype "input"))
      (node (ref "TP72") (pin "1") (pinfunction "1_1") (pintype "passive"))
    )
    (net (code "3") (name "Net-(H1A-A2)") (class "Default")
      (node (ref "H1") (pin "216") (pinfunction "A2_216") (pintype "input"))
      (node (ref "TP216") (pin "1") (pinfunction "1_1") (pintype "passive"))
    )
    (net (code "4") (name "Net-(H1A-A3)") (class "Default")
      (node (ref "H1") (pin "71") (pinfunction "A3_71") (pintype "input"))
      (node (ref "TP71") (pin "1") (pinfunction "1_1") (pintype "passive"))
    )
    (net (code "5") (name "Net-(H1A-A4)") (class "Default")
      (node (ref "H1") (pin "214") (pinfunction "A4_214") (pintype "input"))
      (node (ref "TP214") (pin "1") (pinfunction "1_1") (pintype "passive"))
    )
    (net (code "6") (name "Net-(H1A-A5)") (class "Default")
      (node (ref "H1") (pin "213") (pinfunction "A5_213") (pintype "input"))
      (node (ref "TP213") (pin "1") (pinfunction "1_1") (pintype "passive"))
    )
    (net (code "7") (name "Net-(H1A-A6)") (class "Default")
      (node (ref "H1") (pin "69") (pinfunction "A6_69") (pintype "input"))
      (node (ref "TP69") (pin "1") (pinfunction "1_1") (pintype "passive"))
    )
    (net (code "8") (name "Net-(H1A-A7)") (class "Default")
      (node (ref "H1") (pin "211") (pinfunction "A7_211") (pintype "input"))
      (node (ref "TP211") (pin "1") (pinfunction "1_1") (pintype "passive"))
    )
    (net (code "9") (name "Net-(H1A-A8)") (class "Default")
      (node (ref "H1") (pin "68") (pinfunction "A8_68") (pintype "input"))
      (node (ref "TP68") (pin "1") (pinfunction "1_1") (pintype "passive"))
    )
    (net (code "10") (name "Net-(H1A-A9)") (class "Default")
      (node (ref "H1") (pin "66") (pinfunction "A9_66") (pintype "input"))
      (node (ref "TP66") (pin "1") (pinfunction "1_1") (pintype "passive"))
    )
    (net (code "11") (name "Net-(H1A-A10_AP)") (class "Default")
      (node (ref "H1") (pin "225") (pinfunction "A10_AP_225") (pintype "input"))
      (node (ref "TP225") (pin "1") (pinfunction "1_1") (pintype "passive"))
    )
    (net (code "12") (name "Net-(H1A-A11)") (class "Default")
      (node (ref "H1") (pin "210") (pinfunction "A11_210") (pintype "input"))
      (node (ref "TP210") (pin "1") (pinfunction "1_1") (pintype "passive"))
    )
    (net (code "13") (name "Net-(H1A-A12)") (class "Default")
      (node (ref "H1") (pin "65") (pinfunction "A12_65") (pintype "input"))
      (node (ref "TP65") (pin "1") (pinfunction "1_1") (pintype "passive"))
    )
    (net (code "14") (name "Net-(H1A-A13)") (class "Default")
      (node (ref "H1") (pin "232") (pinfunction "A13_232") (pintype "input"))
      (node (ref "TP232") (pin "1") (pinfunction "1_1") (pintype "passive"))
    )
    (net (code "15") (name "Net-(H1A-A17{slash}NC)") (class "Default")
      (node (ref "H1") (pin "234") (pinfunction "A17/NC_234") (pintype "input"))
      (node (ref "TP234") (pin "1") (pinfunction "1_1") (pintype "passive"))
    )
    (net (code "16") (name "Net-(H1A-CAS_n{slash}A15)") (class "Default")
      (node (ref "H1") (pin "86") (pinfunction "CAS_n/A15_86") (pintype "input"))
      (node (ref "TP86") (pin "1") (pinfunction "1_1") (pintype "passive"))
    )
    (net (code "17") (name "Net-(H1A-RAS_n{slash}A16)") (class "Default")
      (node (ref "H1") (pin "82") (pinfunction "RAS_n/A16_82") (pintype "input"))
      (node (ref "TP82") (pin "1") (pinfunction "1_1") (pintype "passive"))
    )
    (net (code "18") (name "Net-(H1A-WE_n{slash}A14)") (class "Default")
      (node (ref "H1") (pin "228") (pinfunction "WE_n/A14_228") (pintype "input"))
      (node (ref "TP228") (pin "1") (pinfunction "1_1") (pintype "passive"))
    )
    (net (code "19") (name "Net-(H1B-BA0)") (class "Default")
      (node (ref "H1") (pin "81") (pinfunction "BA0_81") (pintype "input"))
      (node (ref "TP81") (pin "1") (pinfunction "1_1") (pintype "passive"))
    )
    (net (code "20") (name "Net-(H1B-BA1)") (class "Default")
      (node (ref "H1") (pin "224") (pinfunction "BA1_224") (pintype "input"))
      (node (ref "TP224") (pin "1") (pinfunction "1_1") (pintype "passive"))
    )
    (net (code "21") (name "Net-(H1C-BG0)") (class "Default")
      (node (ref "H1") (pin "63") (pinfunction "BG0_63") (pintype "input"))
      (node (ref "TP63") (pin "1") (pinfunction "1_1") (pintype "passive"))
    )
    (net (code "22") (name "Net-(H1C-BG1)") (class "Default")
      (node (ref "H1") (pin "207") (pinfunction "BG1_207") (pintype "input"))
      (node (ref "TP207") (pin "1") (pinfunction "1_1") (pintype "passive"))
    )
    (net (code "23") (name "Net-(H1D-CS0_n)") (class "Default")
      (node (ref "H1") (pin "84") (pinfunction "CS0_n_84") (pintype "input"))
      (node (ref "TP84") (pin "1") (pinfunction "1_1") (pintype "passive"))
    )
    (net (code "24") (name "Net-(H1D-CS1_n{slash}NC)") (class "Default")
      (node (ref "H1") (pin "89") (pinfunction "CS1_n/NC_89") (pintype "input"))
      (node (ref "TP89") (pin "1") (pinfunction "1_1") (pintype "passive"))
    )
    (net (code "25") (name "Net-(H1D-CS2_n{slash}C0)") (class "Default")
      (node (ref "H1") (pin "93") (pinfunction "CS2_n/C0_93") (pintype "input"))
      (node (ref "TP93") (pin "1") (pinfunction "1_1") (pintype "passive"))
    )
    (net (code "26") (name "Net-(H1D-CS3_n{slash}C1{slash}NC)") (class "Default")
      (node (ref "H1") (pin "237") (pinfunction "CS3_n/C1/NC_237") (pintype "input"))
      (node (ref "TP237") (pin "1") (pinfunction "1_1") (pintype "passive"))
    )
    (net (code "27") (name "Net-(H1E-CKE0)") (class "Default")
      (node (ref "H1") (pin "60") (pinfunction "CKE0_60") (pintype "input"))
      (node (ref "TP60") (pin "1") (pinfunction "1_1") (pintype "passive"))
    )
    (net (code "28") (name "Net-(H1E-CKE1{slash}NC)") (class "Default")
      (node (ref "H1") (pin "203") (pinfunction "CKE1/NC_203") (pintype "input"))
      (node (ref "TP203") (pin "1") (pinfunction "1_1") (pintype "passive"))
    )
    (net (code "29") (name "Net-(H1F-ODT0)") (class "Default")
      (node (ref "H1") (pin "87") (pinfunction "ODT0_87") (pintype "passive"))
      (node (ref "TP87") (pin "1") (pinfunction "1_1") (pintype "passive"))
    )
    (net (code "30") (name "Net-(H1F-ODT1{slash}NC)") (class "Default")
      (node (ref "H1") (pin "91") (pinfunction "ODT1/NC_91") (pintype "passive"))
      (node (ref "TP91") (pin "1") (pinfunction "1_1") (pintype "passive"))
    )
    (net (code "31") (name "Net-(H1G-ACT_n)") (class "Default")
      (node (ref "H1") (pin "62") (pinfunction "ACT_n_62") (pintype "input"))
      (node (ref "TP62") (pin "1") (pinfunction "1_1") (pintype "passive"))
    )
    (net (code "32") (name "Net-(H1H-DQ0)") (class "Default")
      (node (ref "H1") (pin "5") (pinfunction "DQ0_5") (pintype "bidirectional"))
      (node (ref "TP5") (pin "1") (pinfunction "1_1") (pintype "passive"))
    )
    (net (code "33") (name "Net-(H1H-DQ1)") (class "Default")
      (node (ref "H1") (pin "150") (pinfunction "DQ1_150") (pintype "bidirectional"))
      (node (ref "TP150") (pin "1") (pinfunction "1_1") (pintype "passive"))
    )
    (net (code "34") (name "Net-(H1H-DQ2)") (class "Default")
      (node (ref "H1") (pin "12") (pinfunction "DQ2_12") (pintype "bidirectional"))
      (node (ref "TP12") (pin "1") (pinfunction "1_1") (pintype "passive"))
    )
    (net (code "35") (name "Net-(H1H-DQ3)") (class "Default")
      (node (ref "H1") (pin "157") (pinfunction "DQ3_157") (pintype "bidirectional"))
      (node (ref "TP157") (pin "1") (pinfunction "1_1") (pintype "passive"))
    )
    (net (code "36") (name "Net-(H1H-DQ4)") (class "Default")
      (node (ref "H1") (pin "3") (pinfunction "DQ4_3") (pintype "bidirectional"))
      (node (ref "TP3") (pin "1") (pinfunction "1_1") (pintype "passive"))
    )
    (net (code "37") (name "Net-(H1H-DQ5)") (class "Default")
      (node (ref "H1") (pin "148") (pinfunction "DQ5_148") (pintype "bidirectional"))
      (node (ref "TP148") (pin "1") (pinfunction "1_1") (pintype "passive"))
    )
    (net (code "38") (name "Net-(H1H-DQ6)") (class "Default")
      (node (ref "H1") (pin "10") (pinfunction "DQ6_10") (pintype "bidirectional"))
      (node (ref "TP10") (pin "1") (pinfunction "1_1") (pintype "passive"))
    )
    (net (code "39") (name "Net-(H1H-DQ7)") (class "Default")
      (node (ref "H1") (pin "155") (pinfunction "DQ7_155") (pintype "bidirectional"))
      (node (ref "TP155") (pin "1") (pinfunction "1_1") (pintype "passive"))
    )
    (net (code "40") (name "Net-(H1H-DQ8)") (class "Default")
      (node (ref "H1") (pin "16") (pinfunction "DQ8_16") (pintype "bidirectional"))
      (node (ref "TP16") (pin "1") (pinfunction "1_1") (pintype "passive"))
    )
    (net (code "41") (name "Net-(H1H-DQ9)") (class "Default")
      (node (ref "H1") (pin "161") (pinfunction "DQ9_161") (pintype "bidirectional"))
      (node (ref "TP161") (pin "1") (pinfunction "1_1") (pintype "passive"))
    )
    (net (code "42") (name "Net-(H1H-DQ10)") (class "Default")
      (node (ref "H1") (pin "23") (pinfunction "DQ10_23") (pintype "bidirectional"))
      (node (ref "TP23") (pin "1") (pinfunction "1_1") (pintype "passive"))
    )
    (net (code "43") (name "Net-(H1H-DQ11)") (class "Default")
      (node (ref "H1") (pin "168") (pinfunction "DQ11_168") (pintype "bidirectional"))
      (node (ref "TP168") (pin "1") (pinfunction "1_1") (pintype "passive"))
    )
    (net (code "44") (name "Net-(H1H-DQ12)") (class "Default")
      (node (ref "H1") (pin "14") (pinfunction "DQ12_14") (pintype "bidirectional"))
      (node (ref "TP14") (pin "1") (pinfunction "1_1") (pintype "passive"))
    )
    (net (code "45") (name "Net-(H1H-DQ13)") (class "Default")
      (node (ref "H1") (pin "159") (pinfunction "DQ13_159") (pintype "bidirectional"))
      (node (ref "TP159") (pin "1") (pinfunction "1_1") (pintype "passive"))
    )
    (net (code "46") (name "Net-(H1H-DQ14)") (class "Default")
      (node (ref "H1") (pin "21") (pinfunction "DQ14_21") (pintype "bidirectional"))
      (node (ref "TP21") (pin "1") (pinfunction "1_1") (pintype "passive"))
    )
    (net (code "47") (name "Net-(H1H-DQ15)") (class "Default")
      (node (ref "H1") (pin "166") (pinfunction "DQ15_166") (pintype "bidirectional"))
      (node (ref "TP166") (pin "1") (pinfunction "1_1") (pintype "passive"))
    )
    (net (code "48") (name "Net-(H1H-DQ16)") (class "Default")
      (node (ref "H1") (pin "27") (pinfunction "DQ16_27") (pintype "bidirectional"))
      (node (ref "TP27") (pin "1") (pinfunction "1_1") (pintype "passive"))
    )
    (net (code "49") (name "Net-(H1H-DQ17)") (class "Default")
      (node (ref "H1") (pin "172") (pinfunction "DQ17_172") (pintype "bidirectional"))
      (node (ref "TP172") (pin "1") (pinfunction "1_1") (pintype "passive"))
    )
    (net (code "50") (name "Net-(H1H-DQ18)") (class "Default")
      (node (ref "H1") (pin "34") (pinfunction "DQ18_34") (pintype "bidirectional"))
      (node (ref "TP34") (pin "1") (pinfunction "1_1") (pintype "passive"))
    )
    (net (code "51") (name "Net-(H1H-DQ19)") (class "Default")
      (node (ref "H1") (pin "179") (pinfunction "DQ19_179") (pintype "bidirectional"))
      (node (ref "TP179") (pin "1") (pinfunction "1_1") (pintype "passive"))
    )
    (net (code "52") (name "Net-(H1H-DQ20)") (class "Default")
      (node (ref "H1") (pin "25") (pinfunction "DQ20_25") (pintype "bidirectional"))
      (node (ref "TP25") (pin "1") (pinfunction "1_1") (pintype "passive"))
    )
    (net (code "53") (name "Net-(H1H-DQ21)") (class "Default")
      (node (ref "H1") (pin "170") (pinfunction "DQ21_170") (pintype "bidirectional"))
      (node (ref "TP170") (pin "1") (pinfunction "1_1") (pintype "passive"))
    )
    (net (code "54") (name "Net-(H1H-DQ22)") (class "Default")
      (node (ref "H1") (pin "32") (pinfunction "DQ22_32") (pintype "bidirectional"))
      (node (ref "TP32") (pin "1") (pinfunction "1_1") (pintype "passive"))
    )
    (net (code "55") (name "Net-(H1H-DQ23)") (class "Default")
      (node (ref "H1") (pin "177") (pinfunction "DQ23_177") (pintype "bidirectional"))
      (node (ref "TP177") (pin "1") (pinfunction "1_1") (pintype "passive"))
    )
    (net (code "56") (name "Net-(H1H-DQ24)") (class "Default")
      (node (ref "H1") (pin "38") (pinfunction "DQ24_38") (pintype "bidirectional"))
      (node (ref "TP38") (pin "1") (pinfunction "1_1") (pintype "passive"))
    )
    (net (code "57") (name "Net-(H1H-DQ25)") (class "Default")
      (node (ref "H1") (pin "183") (pinfunction "DQ25_183") (pintype "bidirectional"))
      (node (ref "TP183") (pin "1") (pinfunction "1_1") (pintype "passive"))
    )
    (net (code "58") (name "Net-(H1H-DQ26)") (class "Default")
      (node (ref "H1") (pin "45") (pinfunction "DQ26_45") (pintype "bidirectional"))
      (node (ref "TP45") (pin "1") (pinfunction "1_1") (pintype "passive"))
    )
    (net (code "59") (name "Net-(H1H-DQ27)") (class "Default")
      (node (ref "H1") (pin "190") (pinfunction "DQ27_190") (pintype "bidirectional"))
      (node (ref "TP190") (pin "1") (pinfunction "1_1") (pintype "passive"))
    )
    (net (code "60") (name "Net-(H1H-DQ28)") (class "Default")
      (node (ref "H1") (pin "36") (pinfunction "DQ28_36") (pintype "bidirectional"))
      (node (ref "TP36") (pin "1") (pinfunction "1_1") (pintype "passive"))
    )
    (net (code "61") (name "Net-(H1H-DQ29)") (class "Default")
      (node (ref "H1") (pin "181") (pinfunction "DQ29_181") (pintype "bidirectional"))
      (node (ref "TP181") (pin "1") (pinfunction "1_1") (pintype "passive"))
    )
    (net (code "62") (name "Net-(H1H-DQ30)") (class "Default")
      (node (ref "H1") (pin "43") (pinfunction "DQ30_43") (pintype "bidirectional"))
      (node (ref "TP43") (pin "1") (pinfunction "1_1") (pintype "passive"))
    )
    (net (code "63") (name "Net-(H1H-DQ31)") (class "Default")
      (node (ref "H1") (pin "188") (pinfunction "DQ31_188") (pintype "bidirectional"))
      (node (ref "TP188") (pin "1") (pinfunction "1_1") (pintype "passive"))
    )
    (net (code "64") (name "Net-(H1H-DQ32)") (class "Default")
      (node (ref "H1") (pin "97") (pinfunction "DQ32_97") (pintype "bidirectional"))
      (node (ref "TP97") (pin "1") (pinfunction "1_1") (pintype "passive"))
    )
    (net (code "65") (name "Net-(H1H-DQ33)") (class "Default")
      (node (ref "H1") (pin "242") (pinfunction "DQ33_242") (pintype "bidirectional"))
      (node (ref "TP242") (pin "1") (pinfunction "1_1") (pintype "passive"))
    )
    (net (code "66") (name "Net-(H1H-DQ34)") (class "Default")
      (node (ref "H1") (pin "104") (pinfunction "DQ34_104") (pintype "bidirectional"))
      (node (ref "TP104") (pin "1") (pinfunction "1_1") (pintype "passive"))
    )
    (net (code "67") (name "Net-(H1H-DQ35)") (class "Default")
      (node (ref "H1") (pin "249") (pinfunction "DQ35_249") (pintype "bidirectional"))
      (node (ref "TP249") (pin "1") (pinfunction "1_1") (pintype "passive"))
    )
    (net (code "68") (name "Net-(H1H-DQ36)") (class "Default")
      (node (ref "H1") (pin "95") (pinfunction "DQ36_95") (pintype "bidirectional"))
      (node (ref "TP95") (pin "1") (pinfunction "1_1") (pintype "passive"))
    )
    (net (code "69") (name "Net-(H1H-DQ37)") (class "Default")
      (node (ref "H1") (pin "240") (pinfunction "DQ37_240") (pintype "bidirectional"))
      (node (ref "TP240") (pin "1") (pinfunction "1_1") (pintype "passive"))
    )
    (net (code "70") (name "Net-(H1H-DQ38)") (class "Default")
      (node (ref "H1") (pin "102") (pinfunction "DQ38_102") (pintype "bidirectional"))
      (node (ref "TP102") (pin "1") (pinfunction "1_1") (pintype "passive"))
    )
    (net (code "71") (name "Net-(H1H-DQ39)") (class "Default")
      (node (ref "H1") (pin "247") (pinfunction "DQ39_247") (pintype "bidirectional"))
      (node (ref "TP247") (pin "1") (pinfunction "1_1") (pintype "passive"))
    )
    (net (code "72") (name "Net-(H1H-DQ40)") (class "Default")
      (node (ref "H1") (pin "108") (pinfunction "DQ40_108") (pintype "bidirectional"))
      (node (ref "TP108") (pin "1") (pinfunction "1_1") (pintype "passive"))
    )
    (net (code "73") (name "Net-(H1H-DQ41)") (class "Default")
      (node (ref "H1") (pin "253") (pinfunction "DQ41_253") (pintype "bidirectional"))
      (node (ref "TP253") (pin "1") (pinfunction "1_1") (pintype "passive"))
    )
    (net (code "74") (name "Net-(H1H-DQ42)") (class "Default")
      (node (ref "H1") (pin "115") (pinfunction "DQ42_115") (pintype "bidirectional"))
      (node (ref "TP115") (pin "1") (pinfunction "1_1") (pintype "passive"))
    )
    (net (code "75") (name "Net-(H1H-DQ43)") (class "Default")
      (node (ref "H1") (pin "260") (pinfunction "DQ43_260") (pintype "bidirectional"))
      (node (ref "TP260") (pin "1") (pinfunction "1_1") (pintype "passive"))
    )
    (net (code "76") (name "Net-(H1H-DQ44)") (class "Default")
      (node (ref "H1") (pin "106") (pinfunction "DQ44_106") (pintype "bidirectional"))
      (node (ref "TP106") (pin "1") (pinfunction "1_1") (pintype "passive"))
    )
    (net (code "77") (name "Net-(H1H-DQ45)") (class "Default")
      (node (ref "H1") (pin "251") (pinfunction "DQ45_251") (pintype "bidirectional"))
      (node (ref "TP251") (pin "1") (pinfunction "1_1") (pintype "passive"))
    )
    (net (code "78") (name "Net-(H1H-DQ46)") (class "Default")
      (node (ref "H1") (pin "113") (pinfunction "DQ46_113") (pintype "bidirectional"))
      (node (ref "TP113") (pin "1") (pinfunction "1_1") (pintype "passive"))
    )
    (net (code "79") (name "Net-(H1H-DQ47)") (class "Default")
      (node (ref "H1") (pin "258") (pinfunction "DQ47_258") (pintype "bidirectional"))
      (node (ref "TP258") (pin "1") (pinfunction "1_1") (pintype "passive"))
    )
    (net (code "80") (name "Net-(H1H-DQ48)") (class "Default")
      (node (ref "H1") (pin "119") (pinfunction "DQ48_119") (pintype "bidirectional"))
      (node (ref "TP119") (pin "1") (pinfunction "1_1") (pintype "passive"))
    )
    (net (code "81") (name "Net-(H1H-DQ49)") (class "Default")
      (node (ref "H1") (pin "264") (pinfunction "DQ49_264") (pintype "bidirectional"))
      (node (ref "TP264") (pin "1") (pinfunction "1_1") (pintype "passive"))
    )
    (net (code "82") (name "Net-(H1H-DQ50)") (class "Default")
      (node (ref "H1") (pin "126") (pinfunction "DQ50_126") (pintype "bidirectional"))
      (node (ref "TP126") (pin "1") (pinfunction "1_1") (pintype "passive"))
    )
    (net (code "83") (name "Net-(H1H-DQ51)") (class "Default")
      (node (ref "H1") (pin "271") (pinfunction "DQ51_271") (pintype "bidirectional"))
      (node (ref "TP271") (pin "1") (pinfunction "1_1") (pintype "passive"))
    )
    (net (code "84") (name "Net-(H1H-DQ52)") (class "Default")
      (node (ref "H1") (pin "117") (pinfunction "DQ52_117") (pintype "bidirectional"))
      (node (ref "TP117") (pin "1") (pinfunction "1_1") (pintype "passive"))
    )
    (net (code "85") (name "Net-(H1H-DQ53)") (class "Default")
      (node (ref "H1") (pin "262") (pinfunction "DQ53_262") (pintype "bidirectional"))
      (node (ref "TP262") (pin "1") (pinfunction "1_1") (pintype "passive"))
    )
    (net (code "86") (name "Net-(H1H-DQ54)") (class "Default")
      (node (ref "H1") (pin "124") (pinfunction "DQ54_124") (pintype "bidirectional"))
      (node (ref "TP124") (pin "1") (pinfunction "1_1") (pintype "passive"))
    )
    (net (code "87") (name "Net-(H1H-DQ55)") (class "Default")
      (node (ref "H1") (pin "269") (pinfunction "DQ55_269") (pintype "bidirectional"))
      (node (ref "TP269") (pin "1") (pinfunction "1_1") (pintype "passive"))
    )
    (net (code "88") (name "Net-(H1H-DQ56)") (class "Default")
      (node (ref "H1") (pin "130") (pinfunction "DQ56_130") (pintype "bidirectional"))
      (node (ref "TP130") (pin "1") (pinfunction "1_1") (pintype "passive"))
    )
    (net (code "89") (name "Net-(H1H-DQ57)") (class "Default")
      (node (ref "H1") (pin "275") (pinfunction "DQ57_275") (pintype "bidirectional"))
      (node (ref "TP275") (pin "1") (pinfunction "1_1") (pintype "passive"))
    )
    (net (code "90") (name "Net-(H1H-DQ58)") (class "Default")
      (node (ref "H1") (pin "137") (pinfunction "DQ58_137") (pintype "bidirectional"))
      (node (ref "TP137") (pin "1") (pinfunction "1_1") (pintype "passive"))
    )
    (net (code "91") (name "Net-(H1H-DQ59)") (class "Default")
      (node (ref "H1") (pin "282") (pinfunction "DQ59_282") (pintype "bidirectional"))
      (node (ref "TP282") (pin "1") (pinfunction "1_1") (pintype "passive"))
    )
    (net (code "92") (name "Net-(H1H-DQ60)") (class "Default")
      (node (ref "H1") (pin "128") (pinfunction "DQ60_128") (pintype "bidirectional"))
      (node (ref "TP128") (pin "1") (pinfunction "1_1") (pintype "passive"))
    )
    (net (code "93") (name "Net-(H1H-DQ61)") (class "Default")
      (node (ref "H1") (pin "273") (pinfunction "DQ61_273") (pintype "bidirectional"))
      (node (ref "TP273") (pin "1") (pinfunction "1_1") (pintype "passive"))
    )
    (net (code "94") (name "Net-(H1H-DQ62)") (class "Default")
      (node (ref "H1") (pin "135") (pinfunction "DQ62_135") (pintype "bidirectional"))
      (node (ref "TP135") (pin "1") (pinfunction "1_1") (pintype "passive"))
    )
    (net (code "95") (name "Net-(H1H-DQ63)") (class "Default")
      (node (ref "H1") (pin "280") (pinfunction "DQ63_280") (pintype "bidirectional"))
      (node (ref "TP280") (pin "1") (pinfunction "1_1") (pintype "passive"))
    )
    (net (code "96") (name "Net-(H1I-CB0)") (class "Default")
      (node (ref "H1") (pin "49") (pinfunction "CB0_49") (pintype "passive"))
      (node (ref "TP49") (pin "1") (pinfunction "1_1") (pintype "passive"))
    )
    (net (code "97") (name "Net-(H1I-CB1)") (class "Default")
      (node (ref "H1") (pin "194") (pinfunction "CB1_194") (pintype "passive"))
      (node (ref "TP194") (pin "1") (pinfunction "1_1") (pintype "passive"))
    )
    (net (code "98") (name "Net-(H1I-CB2)") (class "Default")
      (node (ref "H1") (pin "56") (pinfunction "CB2_56") (pintype "passive"))
      (node (ref "TP56") (pin "1") (pinfunction "1_1") (pintype "passive"))
    )
    (net (code "99") (name "Net-(H1I-CB3)") (class "Default")
      (node (ref "H1") (pin "201") (pinfunction "CB3_201") (pintype "passive"))
      (node (ref "TP201") (pin "1") (pinfunction "1_1") (pintype "passive"))
    )
    (net (code "100") (name "Net-(H1I-CB4)") (class "Default")
      (node (ref "H1") (pin "47") (pinfunction "CB4_47") (pintype "passive"))
      (node (ref "TP47") (pin "1") (pinfunction "1_1") (pintype "passive"))
    )
    (net (code "101") (name "Net-(H1I-CB5)") (class "Default")
      (node (ref "H1") (pin "192") (pinfunction "CB5_192") (pintype "passive"))
      (node (ref "TP192") (pin "1") (pinfunction "1_1") (pintype "passive"))
    )
    (net (code "102") (name "Net-(H1I-CB6)") (class "Default")
      (node (ref "H1") (pin "54") (pinfunction "CB6_54") (pintype "passive"))
      (node (ref "TP54") (pin "1") (pinfunction "1_1") (pintype "passive"))
    )
    (net (code "103") (name "Net-(H1I-CB7)") (class "Default")
      (node (ref "H1") (pin "199") (pinfunction "CB7_199") (pintype "passive"))
      (node (ref "TP199") (pin "1") (pinfunction "1_1") (pintype "passive"))
    )
    (net (code "104") (name "Net-(H1J-DQS9_c{slash}TDQS9_c)") (class "Default")
      (node (ref "H1") (pin "8") (pinfunction "DQS9_c/TDQS9_c_8") (pintype "passive"))
      (node (ref "TP8") (pin "1") (pinfunction "1_1") (pintype "passive"))
    )
    (net (code "105") (name "Net-(H1J-DQS9_t{slash}TDQS9_t)") (class "Default")
      (node (ref "H1") (pin "7") (pinfunction "DQS9_t/TDQS9_t_7") (pintype "passive"))
      (node (ref "TP7") (pin "1") (pinfunction "1_1") (pintype "passive"))
    )
    (net (code "106") (name "Net-(H1J-DQS10_c{slash}TDQS10_c)") (class "Default")
      (node (ref "H1") (pin "19") (pinfunction "DQS10_c/TDQS10_c_19") (pintype "passive"))
      (node (ref "TP19") (pin "1") (pinfunction "1_1") (pintype "passive"))
    )
    (net (code "107") (name "Net-(H1J-DQS10_t{slash}TDQS10_t)") (class "Default")
      (node (ref "H1") (pin "18") (pinfunction "DQS10_t/TDQS10_t_18") (pintype "passive"))
      (node (ref "TP18") (pin "1") (pinfunction "1_1") (pintype "passive"))
    )
    (net (code "108") (name "Net-(H1J-DQS11_c{slash}TDQS11_c)") (class "Default")
      (node (ref "H1") (pin "30") (pinfunction "DQS11_c/TDQS11_c_30") (pintype "passive"))
      (node (ref "TP30") (pin "1") (pinfunction "1_1") (pintype "passive"))
    )
    (net (code "109") (name "Net-(H1J-DQS11_t{slash}TDQS11_t)") (class "Default")
      (node (ref "H1") (pin "29") (pinfunction "DQS11_t/TDQS11_t_29") (pintype "passive"))
      (node (ref "TP29") (pin "1") (pinfunction "1_1") (pintype "passive"))
    )
    (net (code "110") (name "Net-(H1J-DQS12_c{slash}TDQS12_c)") (class "Default")
      (node (ref "H1") (pin "41") (pinfunction "DQS12_c/TDQS12_c_41") (pintype "passive"))
      (node (ref "TP41") (pin "1") (pinfunction "1_1") (pintype "passive"))
    )
    (net (code "111") (name "Net-(H1J-DQS12_t{slash}TDQS12_t)") (class "Default")
      (node (ref "H1") (pin "40") (pinfunction "DQS12_t/TDQS12_t_40") (pintype "passive"))
      (node (ref "TP40") (pin "1") (pinfunction "1_1") (pintype "passive"))
    )
    (net (code "112") (name "Net-(H1J-DQS13_c{slash}TDQ13_c)") (class "Default")
      (node (ref "H1") (pin "100") (pinfunction "DQS13_c/TDQ13_c_100") (pintype "passive"))
      (node (ref "TP100") (pin "1") (pinfunction "1_1") (pintype "passive"))
    )
    (net (code "113") (name "Net-(H1J-DQS13_t{slash}TDQ13_t)") (class "Default")
      (node (ref "H1") (pin "99") (pinfunction "DQS13_t/TDQ13_t_99") (pintype "passive"))
      (node (ref "TP99") (pin "1") (pinfunction "1_1") (pintype "passive"))
    )
    (net (code "114") (name "Net-(H1J-DQS14_c{slash}TDQS14_c)") (class "Default")
      (node (ref "H1") (pin "111") (pinfunction "DQS14_c/TDQS14_c_111") (pintype "passive"))
      (node (ref "TP111") (pin "1") (pinfunction "1_1") (pintype "passive"))
    )
    (net (code "115") (name "Net-(H1J-DQS14_t{slash}TDQS14_t)") (class "Default")
      (node (ref "H1") (pin "110") (pinfunction "DQS14_t/TDQS14_t_110") (pintype "passive"))
      (node (ref "TP110") (pin "1") (pinfunction "1_1") (pintype "passive"))
    )
    (net (code "116") (name "Net-(H1J-DQS15_c{slash}TDQS15_c)") (class "Default")
      (node (ref "H1") (pin "122") (pinfunction "DQS15_c/TDQS15_c_122") (pintype "passive"))
      (node (ref "TP122") (pin "1") (pinfunction "1_1") (pintype "passive"))
    )
    (net (code "117") (name "Net-(H1J-DQS15_t{slash}TDQS15_t)") (class "Default")
      (node (ref "H1") (pin "121") (pinfunction "DQS15_t/TDQS15_t_121") (pintype "passive"))
      (node (ref "TP121") (pin "1") (pinfunction "1_1") (pintype "passive"))
    )
    (net (code "118") (name "Net-(H1J-DQS16_c{slash}TDQS16_c)") (class "Default")
      (node (ref "H1") (pin "133") (pinfunction "DQS16_c/TDQS16_c_133") (pintype "passive"))
      (node (ref "TP133") (pin "1") (pinfunction "1_1") (pintype "passive"))
    )
    (net (code "119") (name "Net-(H1J-DQS16_t{slash}TDQS16_t)") (class "Default")
      (node (ref "H1") (pin "132") (pinfunction "DQS16_t/TDQS16_t_132") (pintype "passive"))
      (node (ref "TP132") (pin "1") (pinfunction "1_1") (pintype "passive"))
    )
    (net (code "120") (name "Net-(H1J-DQS17_c{slash}TDQS17_c)") (class "Default")
      (node (ref "H1") (pin "52") (pinfunction "DQS17_c/TDQS17_c_52") (pintype "passive"))
      (node (ref "TP52") (pin "1") (pinfunction "1_1") (pintype "passive"))
    )
    (net (code "121") (name "Net-(H1J-DQS17_t{slash}TDQS17_t)") (class "Default")
      (node (ref "H1") (pin "51") (pinfunction "DQS17_t/TDQS17_t_51") (pintype "passive"))
      (node (ref "TP51") (pin "1") (pinfunction "1_1") (pintype "passive"))
    )
    (net (code "122") (name "Net-(H1K-CK0_c)") (class "Default")
      (node (ref "H1") (pin "75") (pinfunction "CK0_c_75") (pintype "passive"))
      (node (ref "TP75") (pin "1") (pinfunction "1_1") (pintype "passive"))
    )
    (net (code "123") (name "Net-(H1K-CK0_t)") (class "Default")
      (node (ref "H1") (pin "74") (pinfunction "CK0_t_74") (pintype "passive"))
      (node (ref "TP74") (pin "1") (pinfunction "1_1") (pintype "passive"))
    )
    (net (code "124") (name "Net-(H1K-CK1_c)") (class "Default")
      (node (ref "H1") (pin "219") (pinfunction "CK1_c_219") (pintype "passive"))
      (node (ref "TP219") (pin "1") (pinfunction "1_1") (pintype "passive"))
    )
    (net (code "125") (name "Net-(H1K-CK1_t)") (class "Default")
      (node (ref "H1") (pin "218") (pinfunction "CK1_t_218") (pintype "passive"))
      (node (ref "TP218") (pin "1") (pinfunction "1_1") (pintype "passive"))
    )
    (net (code "126") (name "Net-(H1L-PARITY)") (class "Default")
      (node (ref "H1") (pin "222") (pinfunction "PARITY_222") (pintype "passive"))
      (node (ref "TP222") (pin "1") (pinfunction "1_1") (pintype "passive"))
    )
    (net (code "127") (name "Net-(H1N-VDD-Pad59)") (class "Default")
      (node (ref "H1") (pin "59") (pinfunction "VDD_59") (pintype "passive"))
      (node (ref "TP59") (pin "1") (pinfunction "1_1") (pintype "passive"))
    )
    (net (code "128") (name "Net-(H1N-VDD-Pad61)") (class "Default")
      (node (ref "H1") (pin "61") (pinfunction "VDD_61") (pintype "passive"))
      (node (ref "TP61") (pin "1") (pinfunction "1_1") (pintype "passive"))
    )
    (net (code "129") (name "Net-(H1N-VDD-Pad64)") (class "Default")
      (node (ref "H1") (pin "64") (pinfunction "VDD_64") (pintype "passive"))
      (node (ref "TP64") (pin "1") (pinfunction "1_1") (pintype "passive"))
    )
    (net (code "130") (name "Net-(H1N-VDD-Pad67)") (class "Default")
      (node (ref "H1") (pin "67") (pinfunction "VDD_67") (pintype "passive"))
      (node (ref "TP67") (pin "1") (pinfunction "1_1") (pintype "passive"))
    )
    (net (code "131") (name "Net-(H1N-VDD-Pad70)") (class "Default")
      (node (ref "H1") (pin "70") (pinfunction "VDD_70") (pintype "passive"))
      (node (ref "TP70") (pin "1") (pinfunction "1_1") (pintype "passive"))
    )
    (net (code "132") (name "Net-(H1N-VDD-Pad73)") (class "Default")
      (node (ref "H1") (pin "73") (pinfunction "VDD_73") (pintype "passive"))
      (node (ref "TP73") (pin "1") (pinfunction "1_1") (pintype "passive"))
    )
    (net (code "133") (name "Net-(H1N-VDD-Pad76)") (class "Default")
      (node (ref "H1") (pin "76") (pinfunction "VDD_76") (pintype "passive"))
      (node (ref "TP76") (pin "1") (pinfunction "1_1") (pintype "passive"))
    )
    (net (code "134") (name "Net-(H1N-VDD-Pad80)") (class "Default")
      (node (ref "H1") (pin "80") (pinfunction "VDD_80") (pintype "passive"))
      (node (ref "TP80") (pin "1") (pinfunction "1_1") (pintype "passive"))
    )
    (net (code "135") (name "Net-(H1N-VDD-Pad83)") (class "Default")
      (node (ref "H1") (pin "83") (pinfunction "VDD_83") (pintype "passive"))
      (node (ref "TP83") (pin "1") (pinfunction "1_1") (pintype "passive"))
    )
    (net (code "136") (name "Net-(H1N-VDD-Pad85)") (class "Default")
      (node (ref "H1") (pin "85") (pinfunction "VDD_85") (pintype "passive"))
      (node (ref "TP85") (pin "1") (pinfunction "1_1") (pintype "passive"))
    )
    (net (code "137") (name "Net-(H1N-VDD-Pad88)") (class "Default")
      (node (ref "H1") (pin "88") (pinfunction "VDD_88") (pintype "passive"))
      (node (ref "TP88") (pin "1") (pinfunction "1_1") (pintype "passive"))
    )
    (net (code "138") (name "Net-(H1N-VDD-Pad90)") (class "Default")
      (node (ref "H1") (pin "90") (pinfunction "VDD_90") (pintype "passive"))
      (node (ref "TP90") (pin "1") (pinfunction "1_1") (pintype "passive"))
    )
    (net (code "139") (name "Net-(H1N-VDD-Pad92)") (class "Default")
      (node (ref "H1") (pin "92") (pinfunction "VDD_92") (pintype "passive"))
      (node (ref "TP92") (pin "1") (pinfunction "1_1") (pintype "passive"))
    )
    (net (code "140") (name "Net-(H1N-VDD-Pad204)") (class "Default")
      (node (ref "H1") (pin "204") (pinfunction "VDD_204") (pintype "passive"))
      (node (ref "TP204") (pin "1") (pinfunction "1_1") (pintype "passive"))
    )
    (net (code "141") (name "Net-(H1N-VDD-Pad206)") (class "Default")
      (node (ref "H1") (pin "206") (pinfunction "VDD_206") (pintype "passive"))
      (node (ref "TP206") (pin "1") (pinfunction "1_1") (pintype "passive"))
    )
    (net (code "142") (name "Net-(H1N-VDD-Pad209)") (class "Default")
      (node (ref "H1") (pin "209") (pinfunction "VDD_209") (pintype "passive"))
      (node (ref "TP209") (pin "1") (pinfunction "1_1") (pintype "passive"))
    )
    (net (code "143") (name "Net-(H1N-VDD-Pad212)") (class "Default")
      (node (ref "H1") (pin "212") (pinfunction "VDD_212") (pintype "passive"))
      (node (ref "TP212") (pin "1") (pinfunction "1_1") (pintype "passive"))
    )
    (net (code "144") (name "Net-(H1N-VDD-Pad215)") (class "Default")
      (node (ref "H1") (pin "215") (pinfunction "VDD_215") (pintype "passive"))
      (node (ref "TP215") (pin "1") (pinfunction "1_1") (pintype "passive"))
    )
    (net (code "145") (name "Net-(H1N-VDD-Pad217)") (class "Default")
      (node (ref "H1") (pin "217") (pinfunction "VDD_217") (pintype "passive"))
      (node (ref "TP217") (pin "1") (pinfunction "1_1") (pintype "passive"))
    )
    (net (code "146") (name "Net-(H1N-VDD-Pad220)") (class "Default")
      (node (ref "H1") (pin "220") (pinfunction "VDD_220") (pintype "passive"))
      (node (ref "TP220") (pin "1") (pinfunction "1_1") (pintype "passive"))
    )
    (net (code "147") (name "Net-(H1N-VDD-Pad223)") (class "Default")
      (node (ref "H1") (pin "223") (pinfunction "VDD_223") (pintype "passive"))
      (node (ref "TP223") (pin "1") (pinfunction "1_1") (pintype "passive"))
    )
    (net (code "148") (name "Net-(H1N-VDD-Pad226)") (class "Default")
      (node (ref "H1") (pin "226") (pinfunction "VDD_226") (pintype "passive"))
      (node (ref "TP226") (pin "1") (pinfunction "1_1") (pintype "passive"))
    )
    (net (code "149") (name "Net-(H1N-VDD-Pad229)") (class "Default")
      (node (ref "H1") (pin "229") (pinfunction "VDD_229") (pintype "passive"))
      (node (ref "TP229") (pin "1") (pinfunction "1_1") (pintype "passive"))
    )
    (net (code "150") (name "Net-(H1N-VDD-Pad231)") (class "Default")
      (node (ref "H1") (pin "231") (pinfunction "VDD_231") (pintype "passive"))
      (node (ref "TP231") (pin "1") (pinfunction "1_1") (pintype "passive"))
    )
    (net (code "151") (name "Net-(H1N-VDD-Pad233)") (class "Default")
      (node (ref "H1") (pin "233") (pinfunction "VDD_233") (pintype "passive"))
      (node (ref "TP233") (pin "1") (pinfunction "1_1") (pintype "passive"))
    )
    (net (code "152") (name "Net-(H1N-VDD-Pad236)") (class "Default")
      (node (ref "H1") (pin "236") (pinfunction "VDD_236") (pintype "passive"))
      (node (ref "TP236") (pin "1") (pinfunction "1_1") (pintype "passive"))
    )
    (net (code "153") (name "Net-(H1O-VREFCA)") (class "Default")
      (node (ref "H1") (pin "146") (pinfunction "VREFCA_146") (pintype "passive"))
      (node (ref "TP146") (pin "1") (pinfunction "1_1") (pintype "passive"))
    )
    (net (code "154") (name "Net-(H1P-VSS-Pad2)") (class "Default")
      (node (ref "H1") (pin "2") (pinfunction "VSS_2") (pintype "passive"))
      (node (ref "TP2") (pin "1") (pinfunction "1_1") (pintype "passive"))
    )
    (net (code "155") (name "Net-(H1P-VSS-Pad4)") (class "Default")
      (node (ref "H1") (pin "4") (pinfunction "VSS_4") (pintype "passive"))
      (node (ref "TP4") (pin "1") (pinfunction "1_1") (pintype "passive"))
    )
    (net (code "156") (name "Net-(H1P-VSS-Pad6)") (class "Default")
      (node (ref "H1") (pin "6") (pinfunction "VSS_6") (pintype "passive"))
      (node (ref "TP6") (pin "1") (pinfunction "1_1") (pintype "passive"))
    )
    (net (code "157") (name "Net-(H1P-VSS-Pad9)") (class "Default")
      (node (ref "H1") (pin "9") (pinfunction "VSS_9") (pintype "passive"))
      (node (ref "TP9") (pin "1") (pinfunction "1_1") (pintype "passive"))
    )
    (net (code "158") (name "Net-(H1P-VSS-Pad11)") (class "Default")
      (node (ref "H1") (pin "11") (pinfunction "VSS_11") (pintype "passive"))
      (node (ref "TP11") (pin "1") (pinfunction "1_1") (pintype "passive"))
    )
    (net (code "159") (name "Net-(H1P-VSS-Pad13)") (class "Default")
      (node (ref "H1") (pin "13") (pinfunction "VSS_13") (pintype "passive"))
      (node (ref "TP13") (pin "1") (pinfunction "1_1") (pintype "passive"))
    )
    (net (code "160") (name "Net-(H1P-VSS-Pad15)") (class "Default")
      (node (ref "H1") (pin "15") (pinfunction "VSS_15") (pintype "passive"))
      (node (ref "TP15") (pin "1") (pinfunction "1_1") (pintype "passive"))
    )
    (net (code "161") (name "Net-(H1P-VSS-Pad17)") (class "Default")
      (node (ref "H1") (pin "17") (pinfunction "VSS_17") (pintype "passive"))
      (node (ref "TP17") (pin "1") (pinfunction "1_1") (pintype "passive"))
    )
    (net (code "162") (name "Net-(H1P-VSS-Pad20)") (class "Default")
      (node (ref "H1") (pin "20") (pinfunction "VSS_20") (pintype "passive"))
      (node (ref "TP20") (pin "1") (pinfunction "1_1") (pintype "passive"))
    )
    (net (code "163") (name "Net-(H1P-VSS-Pad22)") (class "Default")
      (node (ref "H1") (pin "22") (pinfunction "VSS_22") (pintype "passive"))
      (node (ref "TP22") (pin "1") (pinfunction "1_1") (pintype "passive"))
    )
    (net (code "164") (name "Net-(H1P-VSS-Pad24)") (class "Default")
      (node (ref "H1") (pin "24") (pinfunction "VSS_24") (pintype "passive"))
      (node (ref "TP24") (pin "1") (pinfunction "1_1") (pintype "passive"))
    )
    (net (code "165") (name "Net-(H1P-VSS-Pad26)") (class "Default")
      (node (ref "H1") (pin "26") (pinfunction "VSS_26") (pintype "passive"))
      (node (ref "TP26") (pin "1") (pinfunction "1_1") (pintype "passive"))
    )
    (net (code "166") (name "Net-(H1P-VSS-Pad28)") (class "Default")
      (node (ref "H1") (pin "28") (pinfunction "VSS_28") (pintype "passive"))
      (node (ref "TP28") (pin "1") (pinfunction "1_1") (pintype "passive"))
    )
    (net (code "167") (name "Net-(H1P-VSS-Pad31)") (class "Default")
      (node (ref "H1") (pin "31") (pinfunction "VSS_31") (pintype "passive"))
      (node (ref "TP31") (pin "1") (pinfunction "1_1") (pintype "passive"))
    )
    (net (code "168") (name "Net-(H1P-VSS-Pad33)") (class "Default")
      (node (ref "H1") (pin "33") (pinfunction "VSS_33") (pintype "passive"))
      (node (ref "TP33") (pin "1") (pinfunction "1_1") (pintype "passive"))
    )
    (net (code "169") (name "Net-(H1P-VSS-Pad35)") (class "Default")
      (node (ref "H1") (pin "35") (pinfunction "VSS_35") (pintype "passive"))
      (node (ref "TP35") (pin "1") (pinfunction "1_1") (pintype "passive"))
    )
    (net (code "170") (name "Net-(H1P-VSS-Pad37)") (class "Default")
      (node (ref "H1") (pin "37") (pinfunction "VSS_37") (pintype "passive"))
      (node (ref "TP37") (pin "1") (pinfunction "1_1") (pintype "passive"))
    )
    (net (code "171") (name "Net-(H1P-VSS-Pad39)") (class "Default")
      (node (ref "H1") (pin "39") (pinfunction "VSS_39") (pintype "passive"))
      (node (ref "TP39") (pin "1") (pinfunction "1_1") (pintype "passive"))
    )
    (net (code "172") (name "Net-(H1P-VSS-Pad42)") (class "Default")
      (node (ref "H1") (pin "42") (pinfunction "VSS_42") (pintype "passive"))
      (node (ref "TP42") (pin "1") (pinfunction "1_1") (pintype "passive"))
    )
    (net (code "173") (name "Net-(H1P-VSS-Pad44)") (class "Default")
      (node (ref "H1") (pin "44") (pinfunction "VSS_44") (pintype "passive"))
      (node (ref "TP44") (pin "1") (pinfunction "1_1") (pintype "passive"))
    )
    (net (code "174") (name "Net-(H1P-VSS-Pad46)") (class "Default")
      (node (ref "H1") (pin "46") (pinfunction "VSS_46") (pintype "passive"))
      (node (ref "TP46") (pin "1") (pinfunction "1_1") (pintype "passive"))
    )
    (net (code "175") (name "Net-(H1P-VSS-Pad48)") (class "Default")
      (node (ref "H1") (pin "48") (pinfunction "VSS_48") (pintype "passive"))
      (node (ref "TP48") (pin "1") (pinfunction "1_1") (pintype "passive"))
    )
    (net (code "176") (name "Net-(H1P-VSS-Pad50)") (class "Default")
      (node (ref "H1") (pin "50") (pinfunction "VSS_50") (pintype "passive"))
      (node (ref "TP50") (pin "1") (pinfunction "1_1") (pintype "passive"))
    )
    (net (code "177") (name "Net-(H1P-VSS-Pad53)") (class "Default")
      (node (ref "H1") (pin "53") (pinfunction "VSS_53") (pintype "passive"))
      (node (ref "TP53") (pin "1") (pinfunction "1_1") (pintype "passive"))
    )
    (net (code "178") (name "Net-(H1P-VSS-Pad55)") (class "Default")
      (node (ref "H1") (pin "55") (pinfunction "VSS_55") (pintype "passive"))
      (node (ref "TP55") (pin "1") (pinfunction "1_1") (pintype "passive"))
    )
    (net (code "179") (name "Net-(H1P-VSS-Pad57)") (class "Default")
      (node (ref "H1") (pin "57") (pinfunction "VSS_57") (pintype "passive"))
      (node (ref "TP57") (pin "1") (pinfunction "1_1") (pintype "passive"))
    )
    (net (code "180") (name "Net-(H1P-VSS-Pad94)") (class "Default")
      (node (ref "H1") (pin "94") (pinfunction "VSS_94") (pintype "passive"))
      (node (ref "TP94") (pin "1") (pinfunction "1_1") (pintype "passive"))
    )
    (net (code "181") (name "Net-(H1P-VSS-Pad96)") (class "Default")
      (node (ref "H1") (pin "96") (pinfunction "VSS_96") (pintype "passive"))
      (node (ref "TP96") (pin "1") (pinfunction "1_1") (pintype "passive"))
    )
    (net (code "182") (name "Net-(H1P-VSS-Pad98)") (class "Default")
      (node (ref "H1") (pin "98") (pinfunction "VSS_98") (pintype "passive"))
      (node (ref "TP98") (pin "1") (pinfunction "1_1") (pintype "passive"))
    )
    (net (code "183") (name "Net-(H1P-VSS-Pad101)") (class "Default")
      (node (ref "H1") (pin "101") (pinfunction "VSS_101") (pintype "passive"))
      (node (ref "TP101") (pin "1") (pinfunction "1_1") (pintype "passive"))
    )
    (net (code "184") (name "Net-(H1P-VSS-Pad103)") (class "Default")
      (node (ref "H1") (pin "103") (pinfunction "VSS_103") (pintype "passive"))
      (node (ref "TP103") (pin "1") (pinfunction "1_1") (pintype "passive"))
    )
    (net (code "185") (name "Net-(H1P-VSS-Pad105)") (class "Default")
      (node (ref "H1") (pin "105") (pinfunction "VSS_105") (pintype "passive"))
      (node (ref "TP105") (pin "1") (pinfunction "1_1") (pintype "passive"))
    )
    (net (code "186") (name "Net-(H1P-VSS-Pad107)") (class "Default")
      (node (ref "H1") (pin "107") (pinfunction "VSS_107") (pintype "passive"))
      (node (ref "TP107") (pin "1") (pinfunction "1_1") (pintype "passive"))
    )
    (net (code "187") (name "Net-(H1P-VSS-Pad109)") (class "Default")
      (node (ref "H1") (pin "109") (pinfunction "VSS_109") (pintype "passive"))
      (node (ref "TP109") (pin "1") (pinfunction "1_1") (pintype "passive"))
    )
    (net (code "188") (name "Net-(H1P-VSS-Pad112)") (class "Default")
      (node (ref "H1") (pin "112") (pinfunction "VSS_112") (pintype "passive"))
      (node (ref "TP112") (pin "1") (pinfunction "1_1") (pintype "passive"))
    )
    (net (code "189") (name "Net-(H1P-VSS-Pad114)") (class "Default")
      (node (ref "H1") (pin "114") (pinfunction "VSS_114") (pintype "passive"))
      (node (ref "TP114") (pin "1") (pinfunction "1_1") (pintype "passive"))
    )
    (net (code "190") (name "Net-(H1P-VSS-Pad116)") (class "Default")
      (node (ref "H1") (pin "116") (pinfunction "VSS_116") (pintype "passive"))
      (node (ref "TP116") (pin "1") (pinfunction "1_1") (pintype "passive"))
    )
    (net (code "191") (name "Net-(H1P-VSS-Pad118)") (class "Default")
      (node (ref "H1") (pin "118") (pinfunction "VSS_118") (pintype "passive"))
      (node (ref "TP118") (pin "1") (pinfunction "1_1") (pintype "passive"))
    )
    (net (code "192") (name "Net-(H1P-VSS-Pad120)") (class "Default")
      (node (ref "H1") (pin "120") (pinfunction "VSS_120") (pintype "passive"))
      (node (ref "TP120") (pin "1") (pinfunction "1_1") (pintype "passive"))
    )
    (net (code "193") (name "Net-(H1P-VSS-Pad123)") (class "Default")
      (node (ref "H1") (pin "123") (pinfunction "VSS_123") (pintype "passive"))
      (node (ref "TP123") (pin "1") (pinfunction "1_1") (pintype "passive"))
    )
    (net (code "194") (name "Net-(H1P-VSS-Pad125)") (class "Default")
      (node (ref "H1") (pin "125") (pinfunction "VSS_125") (pintype "passive"))
      (node (ref "TP125") (pin "1") (pinfunction "1_1") (pintype "passive"))
    )
    (net (code "195") (name "Net-(H1P-VSS-Pad127)") (class "Default")
      (node (ref "H1") (pin "127") (pinfunction "VSS_127") (pintype "passive"))
      (node (ref "TP127") (pin "1") (pinfunction "1_1") (pintype "passive"))
    )
    (net (code "196") (name "Net-(H1P-VSS-Pad129)") (class "Default")
      (node (ref "H1") (pin "129") (pinfunction "VSS_129") (pintype "passive"))
      (node (ref "TP129") (pin "1") (pinfunction "1_1") (pintype "passive"))
    )
    (net (code "197") (name "Net-(H1P-VSS-Pad131)") (class "Default")
      (node (ref "H1") (pin "131") (pinfunction "VSS_131") (pintype "passive"))
      (node (ref "TP131") (pin "1") (pinfunction "1_1") (pintype "passive"))
    )
    (net (code "198") (name "Net-(H1P-VSS-Pad134)") (class "Default")
      (node (ref "H1") (pin "134") (pinfunction "VSS_134") (pintype "passive"))
      (node (ref "TP134") (pin "1") (pinfunction "1_1") (pintype "passive"))
    )
    (net (code "199") (name "Net-(H1P-VSS-Pad136)") (class "Default")
      (node (ref "H1") (pin "136") (pinfunction "VSS_136") (pintype "passive"))
      (node (ref "TP136") (pin "1") (pinfunction "1_1") (pintype "passive"))
    )
    (net (code "200") (name "Net-(H1P-VSS-Pad138)") (class "Default")
      (node (ref "H1") (pin "138") (pinfunction "VSS_138") (pintype "passive"))
      (node (ref "TP138") (pin "1") (pinfunction "1_1") (pintype "passive"))
    )
    (net (code "201") (name "Net-(H1P-VSS-Pad147)") (class "Default")
      (node (ref "H1") (pin "147") (pinfunction "VSS_147") (pintype "passive"))
      (node (ref "TP147") (pin "1") (pinfunction "1_1") (pintype "passive"))
    )
    (net (code "202") (name "Net-(H1P-VSS-Pad149)") (class "Default")
      (node (ref "H1") (pin "149") (pinfunction "VSS_149") (pintype "passive"))
      (node (ref "TP149") (pin "1") (pinfunction "1_1") (pintype "passive"))
    )
    (net (code "203") (name "Net-(H1P-VSS-Pad151)") (class "Default")
      (node (ref "H1") (pin "151") (pinfunction "VSS_151") (pintype "passive"))
      (node (ref "TP151") (pin "1") (pinfunction "1_1") (pintype "passive"))
    )
    (net (code "204") (name "Net-(H1P-VSS-Pad154)") (class "Default")
      (node (ref "H1") (pin "154") (pinfunction "VSS_154") (pintype "passive"))
      (node (ref "TP154") (pin "1") (pinfunction "1_1") (pintype "passive"))
    )
    (net (code "205") (name "Net-(H1P-VSS-Pad156)") (class "Default")
      (node (ref "H1") (pin "156") (pinfunction "VSS_156") (pintype "passive"))
      (node (ref "TP156") (pin "1") (pinfunction "1_1") (pintype "passive"))
    )
    (net (code "206") (name "Net-(H1P-VSS-Pad158)") (class "Default")
      (node (ref "H1") (pin "158") (pinfunction "VSS_158") (pintype "passive"))
      (node (ref "TP158") (pin "1") (pinfunction "1_1") (pintype "passive"))
    )
    (net (code "207") (name "Net-(H1P-VSS-Pad160)") (class "Default")
      (node (ref "H1") (pin "160") (pinfunction "VSS_160") (pintype "passive"))
      (node (ref "TP160") (pin "1") (pinfunction "1_1") (pintype "passive"))
    )
    (net (code "208") (name "Net-(H1P-VSS-Pad162)") (class "Default")
      (node (ref "H1") (pin "162") (pinfunction "VSS_162") (pintype "passive"))
      (node (ref "TP162") (pin "1") (pinfunction "1_1") (pintype "passive"))
    )
    (net (code "209") (name "Net-(H1P-VSS-Pad165)") (class "Default")
      (node (ref "H1") (pin "165") (pinfunction "VSS_165") (pintype "passive"))
      (node (ref "TP165") (pin "1") (pinfunction "1_1") (pintype "passive"))
    )
    (net (code "210") (name "Net-(H1P-VSS-Pad167)") (class "Default")
      (node (ref "H1") (pin "167") (pinfunction "VSS_167") (pintype "passive"))
      (node (ref "TP167") (pin "1") (pinfunction "1_1") (pintype "passive"))
    )
    (net (code "211") (name "Net-(H1P-VSS-Pad169)") (class "Default")
      (node (ref "H1") (pin "169") (pinfunction "VSS_169") (pintype "passive"))
      (node (ref "TP169") (pin "1") (pinfunction "1_1") (pintype "passive"))
    )
    (net (code "212") (name "Net-(H1P-VSS-Pad171)") (class "Default")
      (node (ref "H1") (pin "171") (pinfunction "VSS_171") (pintype "passive"))
      (node (ref "TP171") (pin "1") (pinfunction "1_1") (pintype "passive"))
    )
    (net (code "213") (name "Net-(H1P-VSS-Pad173)") (class "Default")
      (node (ref "H1") (pin "173") (pinfunction "VSS_173") (pintype "passive"))
      (node (ref "TP173") (pin "1") (pinfunction "1_1") (pintype "passive"))
    )
    (net (code "214") (name "Net-(H1P-VSS-Pad176)") (class "Default")
      (node (ref "H1") (pin "176") (pinfunction "VSS_176") (pintype "passive"))
      (node (ref "TP176") (pin "1") (pinfunction "1_1") (pintype "passive"))
    )
    (net (code "215") (name "Net-(H1P-VSS-Pad178)") (class "Default")
      (node (ref "H1") (pin "178") (pinfunction "VSS_178") (pintype "passive"))
      (node (ref "TP178") (pin "1") (pinfunction "1_1") (pintype "passive"))
    )
    (net (code "216") (name "Net-(H1P-VSS-Pad180)") (class "Default")
      (node (ref "H1") (pin "180") (pinfunction "VSS_180") (pintype "passive"))
      (node (ref "TP180") (pin "1") (pinfunction "1_1") (pintype "passive"))
    )
    (net (code "217") (name "Net-(H1P-VSS-Pad182)") (class "Default")
      (node (ref "H1") (pin "182") (pinfunction "VSS_182") (pintype "passive"))
      (node (ref "TP182") (pin "1") (pinfunction "1_1") (pintype "passive"))
    )
    (net (code "218") (name "Net-(H1P-VSS-Pad184)") (class "Default")
      (node (ref "H1") (pin "184") (pinfunction "VSS_184") (pintype "passive"))
      (node (ref "TP184") (pin "1") (pinfunction "1_1") (pintype "passive"))
    )
    (net (code "219") (name "Net-(H1P-VSS-Pad187)") (class "Default")
      (node (ref "H1") (pin "187") (pinfunction "VSS_187") (pintype "passive"))
      (node (ref "TP187") (pin "1") (pinfunction "1_1") (pintype "passive"))
    )
    (net (code "220") (name "Net-(H1P-VSS-Pad189)") (class "Default")
      (node (ref "H1") (pin "189") (pinfunction "VSS_189") (pintype "passive"))
      (node (ref "TP189") (pin "1") (pinfunction "1_1") (pintype "passive"))
    )
    (net (code "221") (name "Net-(H1P-VSS-Pad191)") (class "Default")
      (node (ref "H1") (pin "191") (pinfunction "VSS_191") (pintype "passive"))
      (node (ref "TP191") (pin "1") (pinfunction "1_1") (pintype "passive"))
    )
    (net (code "222") (name "Net-(H1P-VSS-Pad193)") (class "Default")
      (node (ref "H1") (pin "193") (pinfunction "VSS_193") (pintype "passive"))
      (node (ref "TP193") (pin "1") (pinfunction "1_1") (pintype "passive"))
    )
    (net (code "223") (name "Net-(H1P-VSS-Pad195)") (class "Default")
      (node (ref "H1") (pin "195") (pinfunction "VSS_195") (pintype "passive"))
      (node (ref "TP195") (pin "1") (pinfunction "1_1") (pintype "passive"))
    )
    (net (code "224") (name "Net-(H1P-VSS-Pad198)") (class "Default")
      (node (ref "H1") (pin "198") (pinfunction "VSS_198") (pintype "passive"))
      (node (ref "TP198") (pin "1") (pinfunction "1_1") (pintype "passive"))
    )
    (net (code "225") (name "Net-(H1P-VSS-Pad200)") (class "Default")
      (node (ref "H1") (pin "200") (pinfunction "VSS_200") (pintype "passive"))
      (node (ref "TP200") (pin "1") (pinfunction "1_1") (pintype "passive"))
    )
    (net (code "226") (name "Net-(H1P-VSS-Pad202)") (class "Default")
      (node (ref "H1") (pin "202") (pinfunction "VSS_202") (pintype "passive"))
      (node (ref "TP202") (pin "1") (pinfunction "1_1") (pintype "passive"))
    )
    (net (code "227") (name "Net-(H1P-VSS-Pad239)") (class "Default")
      (node (ref "H1") (pin "239") (pinfunction "VSS_239") (pintype "passive"))
      (node (ref "TP239") (pin "1") (pinfunction "1_1") (pintype "passive"))
    )
    (net (code "228") (name "Net-(H1P-VSS-Pad241)") (class "Default")
      (node (ref "H1") (pin "241") (pinfunction "VSS_241") (pintype "passive"))
      (node (ref "TP241") (pin "1") (pinfunction "1_1") (pintype "passive"))
    )
    (net (code "229") (name "Net-(H1P-VSS-Pad243)") (class "Default")
      (node (ref "H1") (pin "243") (pinfunction "VSS_243") (pintype "passive"))
      (node (ref "TP243") (pin "1") (pinfunction "1_1") (pintype "passive"))
    )
    (net (code "230") (name "Net-(H1P-VSS-Pad246)") (class "Default")
      (node (ref "H1") (pin "246") (pinfunction "VSS_246") (pintype "passive"))
      (node (ref "TP246") (pin "1") (pinfunction "1_1") (pintype "passive"))
    )
    (net (code "231") (name "Net-(H1P-VSS-Pad248)") (class "Default")
      (node (ref "H1") (pin "248") (pinfunction "VSS_248") (pintype "passive"))
      (node (ref "TP248") (pin "1") (pinfunction "1_1") (pintype "passive"))
    )
    (net (code "232") (name "Net-(H1P-VSS-Pad250)") (class "Default")
      (node (ref "H1") (pin "250") (pinfunction "VSS_250") (pintype "passive"))
      (node (ref "TP250") (pin "1") (pinfunction "1_1") (pintype "passive"))
    )
    (net (code "233") (name "Net-(H1P-VSS-Pad252)") (class "Default")
      (node (ref "H1") (pin "252") (pinfunction "VSS_252") (pintype "passive"))
      (node (ref "TP252") (pin "1") (pinfunction "1_1") (pintype "passive"))
    )
    (net (code "234") (name "Net-(H1P-VSS-Pad254)") (class "Default")
      (node (ref "H1") (pin "254") (pinfunction "VSS_254") (pintype "passive"))
      (node (ref "TP254") (pin "1") (pinfunction "1_1") (pintype "passive"))
    )
    (net (code "235") (name "Net-(H1P-VSS-Pad257)") (class "Default")
      (node (ref "H1") (pin "257") (pinfunction "VSS_257") (pintype "passive"))
      (node (ref "TP257") (pin "1") (pinfunction "1_1") (pintype "passive"))
    )
    (net (code "236") (name "Net-(H1P-VSS-Pad259)") (class "Default")
      (node (ref "H1") (pin "259") (pinfunction "VSS_259") (pintype "passive"))
      (node (ref "TP259") (pin "1") (pinfunction "1_1") (pintype "passive"))
    )
    (net (code "237") (name "Net-(H1P-VSS-Pad261)") (class "Default")
      (node (ref "H1") (pin "261") (pinfunction "VSS_261") (pintype "passive"))
      (node (ref "TP261") (pin "1") (pinfunction "1_1") (pintype "passive"))
    )
    (net (code "238") (name "Net-(H1P-VSS-Pad263)") (class "Default")
      (node (ref "H1") (pin "263") (pinfunction "VSS_263") (pintype "passive"))
      (node (ref "TP263") (pin "1") (pinfunction "1_1") (pintype "passive"))
    )
    (net (code "239") (name "Net-(H1P-VSS-Pad265)") (class "Default")
      (node (ref "H1") (pin "265") (pinfunction "VSS_265") (pintype "passive"))
      (node (ref "TP265") (pin "1") (pinfunction "1_1") (pintype "passive"))
    )
    (net (code "240") (name "Net-(H1P-VSS-Pad268)") (class "Default")
      (node (ref "H1") (pin "268") (pinfunction "VSS_268") (pintype "passive"))
      (node (ref "TP268") (pin "1") (pinfunction "1_1") (pintype "passive"))
    )
    (net (code "241") (name "Net-(H1P-VSS-Pad270)") (class "Default")
      (node (ref "H1") (pin "270") (pinfunction "VSS_270") (pintype "passive"))
      (node (ref "TP270") (pin "1") (pinfunction "1_1") (pintype "passive"))
    )
    (net (code "242") (name "Net-(H1P-VSS-Pad272)") (class "Default")
      (node (ref "H1") (pin "272") (pinfunction "VSS_272") (pintype "passive"))
      (node (ref "TP272") (pin "1") (pinfunction "1_1") (pintype "passive"))
    )
    (net (code "243") (name "Net-(H1P-VSS-Pad274)") (class "Default")
      (node (ref "H1") (pin "274") (pinfunction "VSS_274") (pintype "passive"))
      (node (ref "TP274") (pin "1") (pinfunction "1_1") (pintype "passive"))
    )
    (net (code "244") (name "Net-(H1P-VSS-Pad276)") (class "Default")
      (node (ref "H1") (pin "276") (pinfunction "VSS_276") (pintype "passive"))
      (node (ref "TP276") (pin "1") (pinfunction "1_1") (pintype "passive"))
    )
    (net (code "245") (name "Net-(H1P-VSS-Pad279)") (class "Default")
      (node (ref "H1") (pin "279") (pinfunction "VSS_279") (pintype "passive"))
      (node (ref "TP279") (pin "1") (pinfunction "1_1") (pintype "passive"))
    )
    (net (code "246") (name "Net-(H1P-VSS-Pad281)") (class "Default")
      (node (ref "H1") (pin "281") (pinfunction "VSS_281") (pintype "passive"))
      (node (ref "TP281") (pin "1") (pinfunction "1_1") (pintype "passive"))
    )
    (net (code "247") (name "Net-(H1P-VSS-Pad283)") (class "Default")
      (node (ref "H1") (pin "283") (pinfunction "VSS_283") (pintype "passive"))
      (node (ref "TP283") (pin "1") (pinfunction "1_1") (pintype "passive"))
    )
    (net (code "248") (name "Net-(H1R-VPP-Pad142)") (class "Default")
      (node (ref "H1") (pin "142") (pinfunction "VPP_142") (pintype "passive"))
      (node (ref "TP142") (pin "1") (pinfunction "1_1") (pintype "passive"))
    )
    (net (code "249") (name "Net-(H1R-VPP-Pad143)") (class "Default")
      (node (ref "H1") (pin "143") (pinfunction "VPP_143") (pintype "passive"))
      (node (ref "TP143") (pin "1") (pinfunction "1_1") (pintype "passive"))
    )
    (net (code "250") (name "Net-(H1R-VPP-Pad286)") (class "Default")
      (node (ref "H1") (pin "286") (pinfunction "VPP_286") (pintype "passive"))
      (node (ref "TP286") (pin "1") (pinfunction "1_1") (pintype "passive"))
    )
    (net (code "251") (name "Net-(H1R-VPP-Pad287)") (class "Default")
      (node (ref "H1") (pin "287") (pinfunction "VPP_287") (pintype "passive"))
      (node (ref "TP287") (pin "1") (pinfunction "1_1") (pintype "passive"))
    )
    (net (code "252") (name "Net-(H1R-VPP-Pad288)") (class "Default")
      (node (ref "H1") (pin "288") (pinfunction "VPP_288") (pintype "passive"))
      (node (ref "TP288") (pin "1") (pinfunction "1_1") (pintype "passive"))
    )
    (net (code "253") (name "Net-(H1S-VTT-Pad77)") (class "Default")
      (node (ref "H1") (pin "77") (pinfunction "VTT_77") (pintype "passive"))
      (node (ref "TP77") (pin "1") (pinfunction "1_1") (pintype "passive"))
    )
    (net (code "254") (name "Net-(H1S-VTT-Pad221)") (class "Default")
      (node (ref "H1") (pin "221") (pinfunction "VTT_221") (pintype "passive"))
      (node (ref "TP221") (pin "1") (pinfunction "1_1") (pintype "passive"))
    )
    (net (code "255") (name "Net-(H1T-ALERT_n)") (class "Default")
      (node (ref "H1") (pin "208") (pinfunction "ALERT_n_208") (pintype "passive"))
      (node (ref "TP208") (pin "1") (pinfunction "1_1") (pintype "passive"))
    )
    (net (code "256") (name "Net-(H1T-RESET_n)") (class "Default")
      (node (ref "H1") (pin "58") (pinfunction "RESET_n_58") (pintype "passive"))
      (node (ref "TP58") (pin "1") (pinfunction "1_1") (pintype "passive"))
    )
    (net (code "257") (name "Net-(H1T-RFU-Pad144)") (class "Default")
      (node (ref "H1") (pin "144") (pinfunction "RFU_144") (pintype "passive"))
      (node (ref "TP144") (pin "1") (pinfunction "1_1") (pintype "passive"))
    )
    (net (code "258") (name "Net-(H1T-RFU-Pad205)") (class "Default")
      (node (ref "H1") (pin "205") (pinfunction "RFU_205") (pintype "passive"))
      (node (ref "TP205") (pin "1") (pinfunction "1_1") (pintype "passive"))
    )
    (net (code "259") (name "Net-(H1T-RFU-Pad227)") (class "Default")
      (node (ref "H1") (pin "227") (pinfunction "RFU_227") (pintype "passive"))
      (node (ref "TP227") (pin "1") (pinfunction "1_1") (pintype "passive"))
    )
    (net (code "260") (name "Net-(H1U-DQS0_c)") (class "Default")
      (node (ref "H1") (pin "152") (pinfunction "DQS0_c_152") (pintype "bidirectional"))
      (node (ref "TP152") (pin "1") (pinfunction "1_1") (pintype "passive"))
    )
    (net (code "261") (name "Net-(H1U-DQS0_t)") (class "Default")
      (node (ref "H1") (pin "153") (pinfunction "DQS0_t_153") (pintype "bidirectional"))
      (node (ref "TP153") (pin "1") (pinfunction "1_1") (pintype "passive"))
    )
    (net (code "262") (name "Net-(H1U-DQS1_c)") (class "Default")
      (node (ref "H1") (pin "163") (pinfunction "DQS1_c_163") (pintype "bidirectional"))
      (node (ref "TP163") (pin "1") (pinfunction "1_1") (pintype "passive"))
    )
    (net (code "263") (name "Net-(H1U-DQS1_t)") (class "Default")
      (node (ref "H1") (pin "164") (pinfunction "DQS1_t_164") (pintype "bidirectional"))
      (node (ref "TP164") (pin "1") (pinfunction "1_1") (pintype "passive"))
    )
    (net (code "264") (name "Net-(H1U-DQS2_c)") (class "Default")
      (node (ref "H1") (pin "174") (pinfunction "DQS2_c_174") (pintype "bidirectional"))
      (node (ref "TP174") (pin "1") (pinfunction "1_1") (pintype "passive"))
    )
    (net (code "265") (name "Net-(H1U-DQS2_t)") (class "Default")
      (node (ref "H1") (pin "175") (pinfunction "DQS2_t_175") (pintype "bidirectional"))
      (node (ref "TP175") (pin "1") (pinfunction "1_1") (pintype "passive"))
    )
    (net (code "266") (name "Net-(H1U-DQS3_c)") (class "Default")
      (node (ref "H1") (pin "185") (pinfunction "DQS3_c_185") (pintype "bidirectional"))
      (node (ref "TP185") (pin "1") (pinfunction "1_1") (pintype "passive"))
    )
    (net (code "267") (name "Net-(H1U-DQS3_t)") (class "Default")
      (node (ref "H1") (pin "186") (pinfunction "DQS3_t_186") (pintype "bidirectional"))
      (node (ref "TP186") (pin "1") (pinfunction "1_1") (pintype "passive"))
    )
    (net (code "268") (name "Net-(H1U-DQS4_c)") (class "Default")
      (node (ref "H1") (pin "244") (pinfunction "DQS4_c_244") (pintype "bidirectional"))
      (node (ref "TP244") (pin "1") (pinfunction "1_1") (pintype "passive"))
    )
    (net (code "269") (name "Net-(H1U-DQS4_t)") (class "Default")
      (node (ref "H1") (pin "245") (pinfunction "DQS4_t_245") (pintype "bidirectional"))
      (node (ref "TP245") (pin "1") (pinfunction "1_1") (pintype "passive"))
    )
    (net (code "270") (name "Net-(H1U-DQS5_c)") (class "Default")
      (node (ref "H1") (pin "255") (pinfunction "DQS5_c_255") (pintype "bidirectional"))
      (node (ref "TP255") (pin "1") (pinfunction "1_1") (pintype "passive"))
    )
    (net (code "271") (name "Net-(H1U-DQS5_t)") (class "Default")
      (node (ref "H1") (pin "256") (pinfunction "DQS5_t_256") (pintype "bidirectional"))
      (node (ref "TP256") (pin "1") (pinfunction "1_1") (pintype "passive"))
    )
    (net (code "272") (name "Net-(H1U-DQS6_c)") (class "Default")
      (node (ref "H1") (pin "266") (pinfunction "DQS6_c_266") (pintype "bidirectional"))
      (node (ref "TP266") (pin "1") (pinfunction "1_1") (pintype "passive"))
    )
    (net (code "273") (name "Net-(H1U-DQS6_t)") (class "Default")
      (node (ref "H1") (pin "267") (pinfunction "DQS6_t_267") (pintype "bidirectional"))
      (node (ref "TP267") (pin "1") (pinfunction "1_1") (pintype "passive"))
    )
    (net (code "274") (name "Net-(H1U-DQS7_c)") (class "Default")
      (node (ref "H1") (pin "277") (pinfunction "DQS7_c_277") (pintype "bidirectional"))
      (node (ref "TP277") (pin "1") (pinfunction "1_1") (pintype "passive"))
    )
    (net (code "275") (name "Net-(H1U-DQS7_t)") (class "Default")
      (node (ref "H1") (pin "278") (pinfunction "DQS7_t_278") (pintype "bidirectional"))
      (node (ref "TP278") (pin "1") (pinfunction "1_1") (pintype "passive"))
    )
    (net (code "276") (name "Net-(H1U-DQS8_c)") (class "Default")
      (node (ref "H1") (pin "196") (pinfunction "DQS8_c_196") (pintype "bidirectional"))
      (node (ref "TP196") (pin "1") (pinfunction "1_1") (pintype "passive"))
    )
    (net (code "277") (name "Net-(H1U-DQS8_t)") (class "Default")
      (node (ref "H1") (pin "197") (pinfunction "DQS8_t_197") (pintype "bidirectional"))
      (node (ref "TP197") (pin "1") (pinfunction "1_1") (pintype "passive"))
    )
  )
)
